# SCH_prototypeCarbon_2025-07-03.net
KiCad netlist of a schematic drawn in EasyEDA
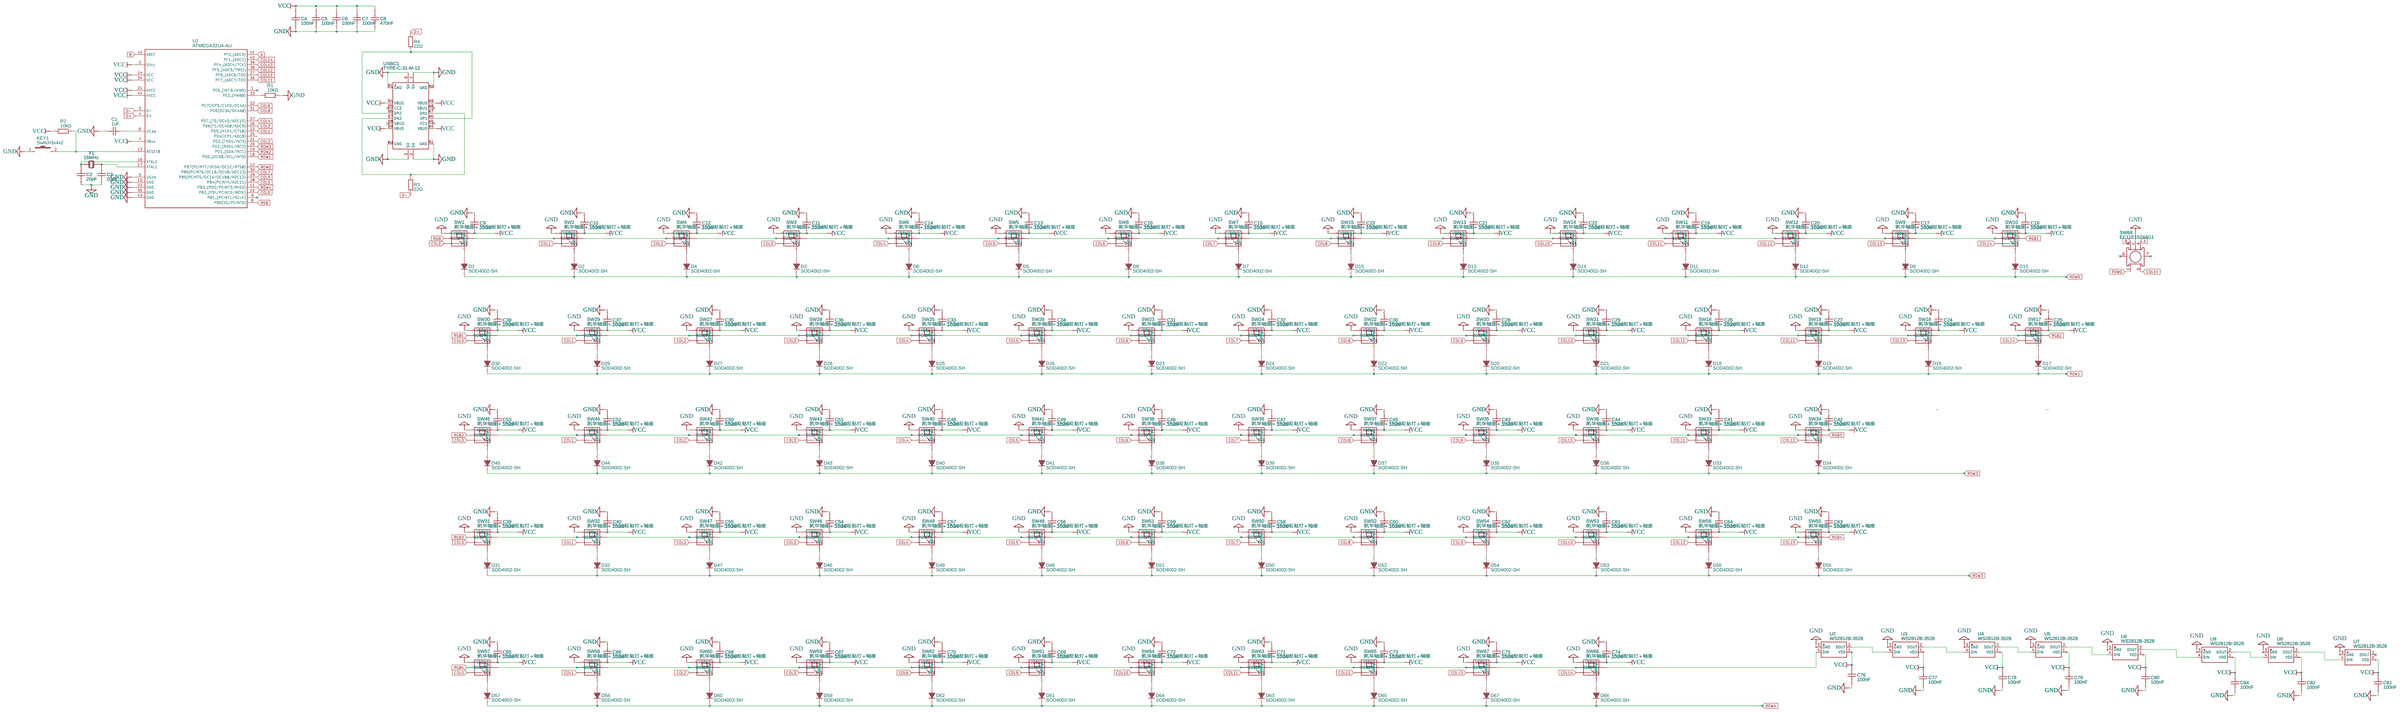
[diagram p0: schematic sheet]

(export (version "E")
  (design (tool "Eeschema 10.0.6"))
  (components
    (comp (ref "C1")
      (value "1uF")
      (fields
        (field (name "Manufacturer Part") "TCC0805X7R105K250FTA")
        (field (name "Manufacturer") "CCTC(三环)")
      )
      (libsource (lib "") (part "TCC0805X7R105K250FTA"))
    )
    (comp (ref "C2")
      (value "20pF")
      (fields
        (field (name "Manufacturer Part") "CC0805JRNPO0BN200")
        (field (name "Manufacturer") "YAGEO(国巨)")
      )
      (libsource (lib "") (part "CC0805JRNPO0BN200"))
    )
    (comp (ref "C3")
      (value "20pF")
      (fields
        (field (name "Manufacturer Part") "CC0805JRNPO0BN200")
        (field (name "Manufacturer") "YAGEO(国巨)")
      )
      (libsource (lib "") (part "CC0805JRNPO0BN200"))
    )
    (comp (ref "C4")
      (value "100nF")
      (fields
        (field (name "Manufacturer Part") "CC0805KRX7R7BB104")
        (field (name "Manufacturer") "YAGEO(国巨)")
      )
      (libsource (lib "") (part "CC0805KRX7R7BB104_1"))
    )
    (comp (ref "C5")
      (value "100nF")
      (fields
        (field (name "Manufacturer Part") "CC0805KRX7R7BB104")
        (field (name "Manufacturer") "YAGEO(国巨)")
      )
      (libsource (lib "") (part "CC0805KRX7R7BB104_1"))
    )
    (comp (ref "C6")
      (value "100nF")
      (fields
        (field (name "Manufacturer Part") "CC0805KRX7R7BB104")
        (field (name "Manufacturer") "YAGEO(国巨)")
      )
      (libsource (lib "") (part "CC0805KRX7R7BB104_1"))
    )
    (comp (ref "C7")
      (value "100nF")
      (fields
        (field (name "Manufacturer Part") "CC0805KRX7R7BB104")
        (field (name "Manufacturer") "YAGEO(国巨)")
      )
      (libsource (lib "") (part "CC0805KRX7R7BB104_1"))
    )
    (comp (ref "C8")
      (value "470nF")
      (fields
        (field (name "Manufacturer Part") "CC0805KKX7R0BB474")
        (field (name "Manufacturer") "YAGEO(国巨)")
      )
      (libsource (lib "") (part "CC0805KKX7R0BB474"))
    )
    (comp (ref "C9")
      (value "100nF")
      (fields
        (field (name "Manufacturer Part") "CC0805KRX7R7BB104")
        (field (name "Manufacturer") "YAGEO(国巨)")
      )
      (libsource (lib "") (part "CC0805KRX7R7BB104"))
    )
    (comp (ref "C10")
      (value "100nF")
      (fields
        (field (name "Manufacturer Part") "CC0805KRX7R7BB104")
        (field (name "Manufacturer") "YAGEO(国巨)")
      )
      (libsource (lib "") (part "CC0805KRX7R7BB104"))
    )
    (comp (ref "C11")
      (value "100nF")
      (fields
        (field (name "Manufacturer Part") "CC0805KRX7R7BB104")
        (field (name "Manufacturer") "YAGEO(国巨)")
      )
      (libsource (lib "") (part "CC0805KRX7R7BB104"))
    )
    (comp (ref "C12")
      (value "100nF")
      (fields
        (field (name "Manufacturer Part") "CC0805KRX7R7BB104")
        (field (name "Manufacturer") "YAGEO(国巨)")
      )
      (libsource (lib "") (part "CC0805KRX7R7BB104"))
    )
    (comp (ref "C13")
      (value "100nF")
      (fields
        (field (name "Manufacturer Part") "CC0805KRX7R7BB104")
        (field (name "Manufacturer") "YAGEO(国巨)")
      )
      (libsource (lib "") (part "CC0805KRX7R7BB104"))
    )
    (comp (ref "C14")
      (value "100nF")
      (fields
        (field (name "Manufacturer Part") "CC0805KRX7R7BB104")
        (field (name "Manufacturer") "YAGEO(国巨)")
      )
      (libsource (lib "") (part "CC0805KRX7R7BB104"))
    )
    (comp (ref "C15")
      (value "100nF")
      (fields
        (field (name "Manufacturer Part") "CC0805KRX7R7BB104")
        (field (name "Manufacturer") "YAGEO(国巨)")
      )
      (libsource (lib "") (part "CC0805KRX7R7BB104"))
    )
    (comp (ref "C16")
      (value "100nF")
      (fields
        (field (name "Manufacturer Part") "CC0805KRX7R7BB104")
        (field (name "Manufacturer") "YAGEO(国巨)")
      )
      (libsource (lib "") (part "CC0805KRX7R7BB104"))
    )
    (comp (ref "C17")
      (value "100nF")
      (fields
        (field (name "Manufacturer Part") "CC0805KRX7R7BB104")
        (field (name "Manufacturer") "YAGEO(国巨)")
      )
      (libsource (lib "") (part "CC0805KRX7R7BB104"))
    )
    (comp (ref "C18")
      (value "100nF")
      (fields
        (field (name "Manufacturer Part") "CC0805KRX7R7BB104")
        (field (name "Manufacturer") "YAGEO(国巨)")
      )
      (libsource (lib "") (part "CC0805KRX7R7BB104"))
    )
    (comp (ref "C19")
      (value "100nF")
      (fields
        (field (name "Manufacturer Part") "CC0805KRX7R7BB104")
        (field (name "Manufacturer") "YAGEO(国巨)")
      )
      (libsource (lib "") (part "CC0805KRX7R7BB104"))
    )
    (comp (ref "C20")
      (value "100nF")
      (fields
        (field (name "Manufacturer Part") "CC0805KRX7R7BB104")
        (field (name "Manufacturer") "YAGEO(国巨)")
      )
      (libsource (lib "") (part "CC0805KRX7R7BB104"))
    )
    (comp (ref "C21")
      (value "100nF")
      (fields
        (field (name "Manufacturer Part") "CC0805KRX7R7BB104")
        (field (name "Manufacturer") "YAGEO(国巨)")
      )
      (libsource (lib "") (part "CC0805KRX7R7BB104"))
    )
    (comp (ref "C22")
      (value "100nF")
      (fields
        (field (name "Manufacturer Part") "CC0805KRX7R7BB104")
        (field (name "Manufacturer") "YAGEO(国巨)")
      )
      (libsource (lib "") (part "CC0805KRX7R7BB104"))
    )
    (comp (ref "C23")
      (value "100nF")
      (fields
        (field (name "Manufacturer Part") "CC0805KRX7R7BB104")
        (field (name "Manufacturer") "YAGEO(国巨)")
      )
      (libsource (lib "") (part "CC0805KRX7R7BB104"))
    )
    (comp (ref "C24")
      (value "100nF")
      (fields
        (field (name "Manufacturer Part") "CC0805KRX7R7BB104")
        (field (name "Manufacturer") "YAGEO(国巨)")
      )
      (libsource (lib "") (part "CC0805KRX7R7BB104"))
    )
    (comp (ref "C25")
      (value "100nF")
      (fields
        (field (name "Manufacturer Part") "CC0805KRX7R7BB104")
        (field (name "Manufacturer") "YAGEO(国巨)")
      )
      (libsource (lib "") (part "CC0805KRX7R7BB104"))
    )
    (comp (ref "C26")
      (value "100nF")
      (fields
        (field (name "Manufacturer Part") "CC0805KRX7R7BB104")
        (field (name "Manufacturer") "YAGEO(国巨)")
      )
      (libsource (lib "") (part "CC0805KRX7R7BB104"))
    )
    (comp (ref "C27")
      (value "100nF")
      (fields
        (field (name "Manufacturer Part") "CC0805KRX7R7BB104")
        (field (name "Manufacturer") "YAGEO(国巨)")
      )
      (libsource (lib "") (part "CC0805KRX7R7BB104"))
    )
    (comp (ref "C28")
      (value "100nF")
      (fields
        (field (name "Manufacturer Part") "CC0805KRX7R7BB104")
        (field (name "Manufacturer") "YAGEO(国巨)")
      )
      (libsource (lib "") (part "CC0805KRX7R7BB104"))
    )
    (comp (ref "C29")
      (value "100nF")
      (fields
        (field (name "Manufacturer Part") "CC0805KRX7R7BB104")
        (field (name "Manufacturer") "YAGEO(国巨)")
      )
      (libsource (lib "") (part "CC0805KRX7R7BB104"))
    )
    (comp (ref "C30")
      (value "100nF")
      (fields
        (field (name "Manufacturer Part") "CC0805KRX7R7BB104")
        (field (name "Manufacturer") "YAGEO(国巨)")
      )
      (libsource (lib "") (part "CC0805KRX7R7BB104"))
    )
    (comp (ref "C31")
      (value "100nF")
      (fields
        (field (name "Manufacturer Part") "CC0805KRX7R7BB104")
        (field (name "Manufacturer") "YAGEO(国巨)")
      )
      (libsource (lib "") (part "CC0805KRX7R7BB104"))
    )
    (comp (ref "C32")
      (value "100nF")
      (fields
        (field (name "Manufacturer Part") "CC0805KRX7R7BB104")
        (field (name "Manufacturer") "YAGEO(国巨)")
      )
      (libsource (lib "") (part "CC0805KRX7R7BB104"))
    )
    (comp (ref "C33")
      (value "100nF")
      (fields
        (field (name "Manufacturer Part") "CC0805KRX7R7BB104")
        (field (name "Manufacturer") "YAGEO(国巨)")
      )
      (libsource (lib "") (part "CC0805KRX7R7BB104"))
    )
    (comp (ref "C34")
      (value "100nF")
      (fields
        (field (name "Manufacturer Part") "CC0805KRX7R7BB104")
        (field (name "Manufacturer") "YAGEO(国巨)")
      )
      (libsource (lib "") (part "CC0805KRX7R7BB104"))
    )
    (comp (ref "C35")
      (value "100nF")
      (fields
        (field (name "Manufacturer Part") "CC0805KRX7R7BB104")
        (field (name "Manufacturer") "YAGEO(国巨)")
      )
      (libsource (lib "") (part "CC0805KRX7R7BB104"))
    )
    (comp (ref "C36")
      (value "100nF")
      (fields
        (field (name "Manufacturer Part") "CC0805KRX7R7BB104")
        (field (name "Manufacturer") "YAGEO(国巨)")
      )
      (libsource (lib "") (part "CC0805KRX7R7BB104"))
    )
    (comp (ref "C37")
      (value "100nF")
      (fields
        (field (name "Manufacturer Part") "CC0805KRX7R7BB104")
        (field (name "Manufacturer") "YAGEO(国巨)")
      )
      (libsource (lib "") (part "CC0805KRX7R7BB104"))
    )
    (comp (ref "C38")
      (value "100nF")
      (fields
        (field (name "Manufacturer Part") "CC0805KRX7R7BB104")
        (field (name "Manufacturer") "YAGEO(国巨)")
      )
      (libsource (lib "") (part "CC0805KRX7R7BB104"))
    )
    (comp (ref "C39")
      (value "100nF")
      (fields
        (field (name "Manufacturer Part") "CC0805KRX7R7BB104")
        (field (name "Manufacturer") "YAGEO(国巨)")
      )
      (libsource (lib "") (part "CC0805KRX7R7BB104"))
    )
    (comp (ref "C40")
      (value "100nF")
      (fields
        (field (name "Manufacturer Part") "CC0805KRX7R7BB104")
        (field (name "Manufacturer") "YAGEO(国巨)")
      )
      (libsource (lib "") (part "CC0805KRX7R7BB104"))
    )
    (comp (ref "C41")
      (value "100nF")
      (fields
        (field (name "Manufacturer Part") "CC0805KRX7R7BB104")
        (field (name "Manufacturer") "YAGEO(国巨)")
      )
      (libsource (lib "") (part "CC0805KRX7R7BB104"))
    )
    (comp (ref "C42")
      (value "100nF")
      (fields
        (field (name "Manufacturer Part") "CC0805KRX7R7BB104")
        (field (name "Manufacturer") "YAGEO(国巨)")
      )
      (libsource (lib "") (part "CC0805KRX7R7BB104"))
    )
    (comp (ref "C43")
      (value "100nF")
      (fields
        (field (name "Manufacturer Part") "CC0805KRX7R7BB104")
        (field (name "Manufacturer") "YAGEO(国巨)")
      )
      (libsource (lib "") (part "CC0805KRX7R7BB104"))
    )
    (comp (ref "C44")
      (value "100nF")
      (fields
        (field (name "Manufacturer Part") "CC0805KRX7R7BB104")
        (field (name "Manufacturer") "YAGEO(国巨)")
      )
      (libsource (lib "") (part "CC0805KRX7R7BB104"))
    )
    (comp (ref "C45")
      (value "100nF")
      (fields
        (field (name "Manufacturer Part") "CC0805KRX7R7BB104")
        (field (name "Manufacturer") "YAGEO(国巨)")
      )
      (libsource (lib "") (part "CC0805KRX7R7BB104"))
    )
    (comp (ref "C46")
      (value "100nF")
      (fields
        (field (name "Manufacturer Part") "CC0805KRX7R7BB104")
        (field (name "Manufacturer") "YAGEO(国巨)")
      )
      (libsource (lib "") (part "CC0805KRX7R7BB104"))
    )
    (comp (ref "C47")
      (value "100nF")
      (fields
        (field (name "Manufacturer Part") "CC0805KRX7R7BB104")
        (field (name "Manufacturer") "YAGEO(国巨)")
      )
      (libsource (lib "") (part "CC0805KRX7R7BB104"))
    )
    (comp (ref "C48")
      (value "100nF")
      (fields
        (field (name "Manufacturer Part") "CC0805KRX7R7BB104")
        (field (name "Manufacturer") "YAGEO(国巨)")
      )
      (libsource (lib "") (part "CC0805KRX7R7BB104"))
    )
    (comp (ref "C49")
      (value "100nF")
      (fields
        (field (name "Manufacturer Part") "CC0805KRX7R7BB104")
        (field (name "Manufacturer") "YAGEO(国巨)")
      )
      (libsource (lib "") (part "CC0805KRX7R7BB104"))
    )
    (comp (ref "C50")
      (value "100nF")
      (fields
        (field (name "Manufacturer Part") "CC0805KRX7R7BB104")
        (field (name "Manufacturer") "YAGEO(国巨)")
      )
      (libsource (lib "") (part "CC0805KRX7R7BB104"))
    )
    (comp (ref "C51")
      (value "100nF")
      (fields
        (field (name "Manufacturer Part") "CC0805KRX7R7BB104")
        (field (name "Manufacturer") "YAGEO(国巨)")
      )
      (libsource (lib "") (part "CC0805KRX7R7BB104"))
    )
    (comp (ref "C52")
      (value "100nF")
      (fields
        (field (name "Manufacturer Part") "CC0805KRX7R7BB104")
        (field (name "Manufacturer") "YAGEO(国巨)")
      )
      (libsource (lib "") (part "CC0805KRX7R7BB104"))
    )
    (comp (ref "C53")
      (value "100nF")
      (fields
        (field (name "Manufacturer Part") "CC0805KRX7R7BB104")
        (field (name "Manufacturer") "YAGEO(国巨)")
      )
      (libsource (lib "") (part "CC0805KRX7R7BB104"))
    )
    (comp (ref "C54")
      (value "100nF")
      (fields
        (field (name "Manufacturer Part") "CC0805KRX7R7BB104")
        (field (name "Manufacturer") "YAGEO(国巨)")
      )
      (libsource (lib "") (part "CC0805KRX7R7BB104"))
    )
    (comp (ref "C55")
      (value "100nF")
      (fields
        (field (name "Manufacturer Part") "CC0805KRX7R7BB104")
        (field (name "Manufacturer") "YAGEO(国巨)")
      )
      (libsource (lib "") (part "CC0805KRX7R7BB104"))
    )
    (comp (ref "C56")
      (value "100nF")
      (fields
        (field (name "Manufacturer Part") "CC0805KRX7R7BB104")
        (field (name "Manufacturer") "YAGEO(国巨)")
      )
      (libsource (lib "") (part "CC0805KRX7R7BB104"))
    )
    (comp (ref "C57")
      (value "100nF")
      (fields
        (field (name "Manufacturer Part") "CC0805KRX7R7BB104")
        (field (name "Manufacturer") "YAGEO(国巨)")
      )
      (libsource (lib "") (part "CC0805KRX7R7BB104"))
    )
    (comp (ref "C58")
      (value "100nF")
      (fields
        (field (name "Manufacturer Part") "CC0805KRX7R7BB104")
        (field (name "Manufacturer") "YAGEO(国巨)")
      )
      (libsource (lib "") (part "CC0805KRX7R7BB104"))
    )
    (comp (ref "C59")
      (value "100nF")
      (fields
        (field (name "Manufacturer Part") "CC0805KRX7R7BB104")
        (field (name "Manufacturer") "YAGEO(国巨)")
      )
      (libsource (lib "") (part "CC0805KRX7R7BB104"))
    )
    (comp (ref "C60")
      (value "100nF")
      (fields
        (field (name "Manufacturer Part") "CC0805KRX7R7BB104")
        (field (name "Manufacturer") "YAGEO(国巨)")
      )
      (libsource (lib "") (part "CC0805KRX7R7BB104"))
    )
    (comp (ref "C61")
      (value "100nF")
      (fields
        (field (name "Manufacturer Part") "CC0805KRX7R7BB104")
        (field (name "Manufacturer") "YAGEO(国巨)")
      )
      (libsource (lib "") (part "CC0805KRX7R7BB104"))
    )
    (comp (ref "C62")
      (value "100nF")
      (fields
        (field (name "Manufacturer Part") "CC0805KRX7R7BB104")
        (field (name "Manufacturer") "YAGEO(国巨)")
      )
      (libsource (lib "") (part "CC0805KRX7R7BB104"))
    )
    (comp (ref "C63")
      (value "100nF")
      (fields
        (field (name "Manufacturer Part") "CC0805KRX7R7BB104")
        (field (name "Manufacturer") "YAGEO(国巨)")
      )
      (libsource (lib "") (part "CC0805KRX7R7BB104"))
    )
    (comp (ref "C64")
      (value "100nF")
      (fields
        (field (name "Manufacturer Part") "CC0805KRX7R7BB104")
        (field (name "Manufacturer") "YAGEO(国巨)")
      )
      (libsource (lib "") (part "CC0805KRX7R7BB104"))
    )
    (comp (ref "C65")
      (value "100nF")
      (fields
        (field (name "Manufacturer Part") "CC0805KRX7R7BB104")
        (field (name "Manufacturer") "YAGEO(国巨)")
      )
      (libsource (lib "") (part "CC0805KRX7R7BB104"))
    )
    (comp (ref "C66")
      (value "100nF")
      (fields
        (field (name "Manufacturer Part") "CC0805KRX7R7BB104")
        (field (name "Manufacturer") "YAGEO(国巨)")
      )
      (libsource (lib "") (part "CC0805KRX7R7BB104"))
    )
    (comp (ref "C67")
      (value "100nF")
      (fields
        (field (name "Manufacturer Part") "CC0805KRX7R7BB104")
        (field (name "Manufacturer") "YAGEO(国巨)")
      )
      (libsource (lib "") (part "CC0805KRX7R7BB104"))
    )
    (comp (ref "C68")
      (value "100nF")
      (fields
        (field (name "Manufacturer Part") "CC0805KRX7R7BB104")
        (field (name "Manufacturer") "YAGEO(国巨)")
      )
      (libsource (lib "") (part "CC0805KRX7R7BB104"))
    )
    (comp (ref "C69")
      (value "100nF")
      (fields
        (field (name "Manufacturer Part") "CC0805KRX7R7BB104")
        (field (name "Manufacturer") "YAGEO(国巨)")
      )
      (libsource (lib "") (part "CC0805KRX7R7BB104"))
    )
    (comp (ref "C70")
      (value "100nF")
      (fields
        (field (name "Manufacturer Part") "CC0805KRX7R7BB104")
        (field (name "Manufacturer") "YAGEO(国巨)")
      )
      (libsource (lib "") (part "CC0805KRX7R7BB104"))
    )
    (comp (ref "C71")
      (value "100nF")
      (fields
        (field (name "Manufacturer Part") "CC0805KRX7R7BB104")
        (field (name "Manufacturer") "YAGEO(国巨)")
      )
      (libsource (lib "") (part "CC0805KRX7R7BB104"))
    )
    (comp (ref "C72")
      (value "100nF")
      (fields
        (field (name "Manufacturer Part") "CC0805KRX7R7BB104")
        (field (name "Manufacturer") "YAGEO(国巨)")
      )
      (libsource (lib "") (part "CC0805KRX7R7BB104"))
    )
    (comp (ref "C73")
      (value "100nF")
      (fields
        (field (name "Manufacturer Part") "CC0805KRX7R7BB104")
        (field (name "Manufacturer") "YAGEO(国巨)")
      )
      (libsource (lib "") (part "CC0805KRX7R7BB104"))
    )
    (comp (ref "C74")
      (value "100nF")
      (fields
        (field (name "Manufacturer Part") "CC0805KRX7R7BB104")
        (field (name "Manufacturer") "YAGEO(国巨)")
      )
      (libsource (lib "") (part "CC0805KRX7R7BB104"))
    )
    (comp (ref "C75")
      (value "100nF")
      (fields
        (field (name "Manufacturer Part") "CC0805KRX7R7BB104")
        (field (name "Manufacturer") "YAGEO(国巨)")
      )
      (libsource (lib "") (part "CC0805KRX7R7BB104"))
    )
    (comp (ref "C76")
      (value "100nF")
      (fields
        (field (name "Manufacturer Part") "CC0805KRX7R7BB104")
        (field (name "Manufacturer") "YAGEO(国巨)")
      )
      (libsource (lib "") (part "CC0805KRX7R7BB104"))
    )
    (comp (ref "C77")
      (value "100nF")
      (fields
        (field (name "Manufacturer Part") "CC0805KRX7R7BB104")
        (field (name "Manufacturer") "YAGEO(国巨)")
      )
      (libsource (lib "") (part "CC0805KRX7R7BB104"))
    )
    (comp (ref "C78")
      (value "100nF")
      (fields
        (field (name "Manufacturer Part") "CC0805KRX7R7BB104")
        (field (name "Manufacturer") "YAGEO(国巨)")
      )
      (libsource (lib "") (part "CC0805KRX7R7BB104"))
    )
    (comp (ref "C79")
      (value "100nF")
      (fields
        (field (name "Manufacturer Part") "CC0805KRX7R7BB104")
        (field (name "Manufacturer") "YAGEO(国巨)")
      )
      (libsource (lib "") (part "CC0805KRX7R7BB104"))
    )
    (comp (ref "C80")
      (value "100nF")
      (fields
        (field (name "Manufacturer Part") "CC0805KRX7R7BB104")
        (field (name "Manufacturer") "YAGEO(国巨)")
      )
      (libsource (lib "") (part "CC0805KRX7R7BB104"))
    )
    (comp (ref "C81")
      (value "100nF")
      (fields
        (field (name "Manufacturer Part") "CC0805KRX7R7BB104")
        (field (name "Manufacturer") "YAGEO(国巨)")
      )
      (libsource (lib "") (part "CC0805KRX7R7BB104"))
    )
    (comp (ref "C82")
      (value "100nF")
      (fields
        (field (name "Manufacturer Part") "CC0805KRX7R7BB104")
        (field (name "Manufacturer") "YAGEO(国巨)")
      )
      (libsource (lib "") (part "CC0805KRX7R7BB104"))
    )
    (comp (ref "C84")
      (value "100nF")
      (fields
        (field (name "Manufacturer Part") "CC0805KRX7R7BB104")
        (field (name "Manufacturer") "YAGEO(国巨)")
      )
      (libsource (lib "") (part "CC0805KRX7R7BB104"))
    )
    (comp (ref "D1")
      (value "SOD4002-SH")
      (fields (field (name "Manufacturer") "LRC(乐山无线电)"))
      (libsource (lib "") (part "SOD4002-SH"))
    )
    (comp (ref "D2")
      (value "SOD4002-SH")
      (fields (field (name "Manufacturer") "LRC(乐山无线电)"))
      (libsource (lib "") (part "SOD4002-SH"))
    )
    (comp (ref "D3")
      (value "SOD4002-SH")
      (fields (field (name "Manufacturer") "LRC(乐山无线电)"))
      (libsource (lib "") (part "SOD4002-SH"))
    )
    (comp (ref "D4")
      (value "SOD4002-SH")
      (fields (field (name "Manufacturer") "LRC(乐山无线电)"))
      (libsource (lib "") (part "SOD4002-SH"))
    )
    (comp (ref "D5")
      (value "SOD4002-SH")
      (fields (field (name "Manufacturer") "LRC(乐山无线电)"))
      (libsource (lib "") (part "SOD4002-SH"))
    )
    (comp (ref "D6")
      (value "SOD4002-SH")
      (fields (field (name "Manufacturer") "LRC(乐山无线电)"))
      (libsource (lib "") (part "SOD4002-SH"))
    )
    (comp (ref "D7")
      (value "SOD4002-SH")
      (fields (field (name "Manufacturer") "LRC(乐山无线电)"))
      (libsource (lib "") (part "SOD4002-SH"))
    )
    (comp (ref "D8")
      (value "SOD4002-SH")
      (fields (field (name "Manufacturer") "LRC(乐山无线电)"))
      (libsource (lib "") (part "SOD4002-SH"))
    )
    (comp (ref "D9")
      (value "SOD4002-SH")
      (fields (field (name "Manufacturer") "LRC(乐山无线电)"))
      (libsource (lib "") (part "SOD4002-SH"))
    )
    (comp (ref "D10")
      (value "SOD4002-SH")
      (fields (field (name "Manufacturer") "LRC(乐山无线电)"))
      (libsource (lib "") (part "SOD4002-SH"))
    )
    (comp (ref "D11")
      (value "SOD4002-SH")
      (fields (field (name "Manufacturer") "LRC(乐山无线电)"))
      (libsource (lib "") (part "SOD4002-SH"))
    )
    (comp (ref "D12")
      (value "SOD4002-SH")
      (fields (field (name "Manufacturer") "LRC(乐山无线电)"))
      (libsource (lib "") (part "SOD4002-SH"))
    )
    (comp (ref "D13")
      (value "SOD4002-SH")
      (fields (field (name "Manufacturer") "LRC(乐山无线电)"))
      (libsource (lib "") (part "SOD4002-SH"))
    )
    (comp (ref "D14")
      (value "SOD4002-SH")
      (fields (field (name "Manufacturer") "LRC(乐山无线电)"))
      (libsource (lib "") (part "SOD4002-SH"))
    )
    (comp (ref "D15")
      (value "SOD4002-SH")
      (fields (field (name "Manufacturer") "LRC(乐山无线电)"))
      (libsource (lib "") (part "SOD4002-SH"))
    )
    (comp (ref "D16")
      (value "SOD4002-SH")
      (fields (field (name "Manufacturer") "LRC(乐山无线电)"))
      (libsource (lib "") (part "SOD4002-SH"))
    )
    (comp (ref "D17")
      (value "SOD4002-SH")
      (fields (field (name "Manufacturer") "LRC(乐山无线电)"))
      (libsource (lib "") (part "SOD4002-SH"))
    )
    (comp (ref "D18")
      (value "SOD4002-SH")
      (fields (field (name "Manufacturer") "LRC(乐山无线电)"))
      (libsource (lib "") (part "SOD4002-SH"))
    )
    (comp (ref "D19")
      (value "SOD4002-SH")
      (fields (field (name "Manufacturer") "LRC(乐山无线电)"))
      (libsource (lib "") (part "SOD4002-SH"))
    )
    (comp (ref "D20")
      (value "SOD4002-SH")
      (fields (field (name "Manufacturer") "LRC(乐山无线电)"))
      (libsource (lib "") (part "SOD4002-SH"))
    )
    (comp (ref "D21")
      (value "SOD4002-SH")
      (fields (field (name "Manufacturer") "LRC(乐山无线电)"))
      (libsource (lib "") (part "SOD4002-SH"))
    )
    (comp (ref "D22")
      (value "SOD4002-SH")
      (fields (field (name "Manufacturer") "LRC(乐山无线电)"))
      (libsource (lib "") (part "SOD4002-SH"))
    )
    (comp (ref "D23")
      (value "SOD4002-SH")
      (fields (field (name "Manufacturer") "LRC(乐山无线电)"))
      (libsource (lib "") (part "SOD4002-SH"))
    )
    (comp (ref "D24")
      (value "SOD4002-SH")
      (fields (field (name "Manufacturer") "LRC(乐山无线电)"))
      (libsource (lib "") (part "SOD4002-SH"))
    )
    (comp (ref "D25")
      (value "SOD4002-SH")
      (fields (field (name "Manufacturer") "LRC(乐山无线电)"))
      (libsource (lib "") (part "SOD4002-SH"))
    )
    (comp (ref "D26")
      (value "SOD4002-SH")
      (fields (field (name "Manufacturer") "LRC(乐山无线电)"))
      (libsource (lib "") (part "SOD4002-SH"))
    )
    (comp (ref "D27")
      (value "SOD4002-SH")
      (fields (field (name "Manufacturer") "LRC(乐山无线电)"))
      (libsource (lib "") (part "SOD4002-SH"))
    )
    (comp (ref "D28")
      (value "SOD4002-SH")
      (fields (field (name "Manufacturer") "LRC(乐山无线电)"))
      (libsource (lib "") (part "SOD4002-SH"))
    )
    (comp (ref "D29")
      (value "SOD4002-SH")
      (fields (field (name "Manufacturer") "LRC(乐山无线电)"))
      (libsource (lib "") (part "SOD4002-SH"))
    )
    (comp (ref "D30")
      (value "SOD4002-SH")
      (fields (field (name "Manufacturer") "LRC(乐山无线电)"))
      (libsource (lib "") (part "SOD4002-SH"))
    )
    (comp (ref "D31")
      (value "SOD4002-SH")
      (fields (field (name "Manufacturer") "LRC(乐山无线电)"))
      (libsource (lib "") (part "SOD4002-SH"))
    )
    (comp (ref "D32")
      (value "SOD4002-SH")
      (fields (field (name "Manufacturer") "LRC(乐山无线电)"))
      (libsource (lib "") (part "SOD4002-SH"))
    )
    (comp (ref "D33")
      (value "SOD4002-SH")
      (fields (field (name "Manufacturer") "LRC(乐山无线电)"))
      (libsource (lib "") (part "SOD4002-SH"))
    )
    (comp (ref "D34")
      (value "SOD4002-SH")
      (fields (field (name "Manufacturer") "LRC(乐山无线电)"))
      (libsource (lib "") (part "SOD4002-SH"))
    )
    (comp (ref "D35")
      (value "SOD4002-SH")
      (fields (field (name "Manufacturer") "LRC(乐山无线电)"))
      (libsource (lib "") (part "SOD4002-SH"))
    )
    (comp (ref "D36")
      (value "SOD4002-SH")
      (fields (field (name "Manufacturer") "LRC(乐山无线电)"))
      (libsource (lib "") (part "SOD4002-SH"))
    )
    (comp (ref "D37")
      (value "SOD4002-SH")
      (fields (field (name "Manufacturer") "LRC(乐山无线电)"))
      (libsource (lib "") (part "SOD4002-SH"))
    )
    (comp (ref "D38")
      (value "SOD4002-SH")
      (fields (field (name "Manufacturer") "LRC(乐山无线电)"))
      (libsource (lib "") (part "SOD4002-SH"))
    )
    (comp (ref "D39")
      (value "SOD4002-SH")
      (fields (field (name "Manufacturer") "LRC(乐山无线电)"))
      (libsource (lib "") (part "SOD4002-SH"))
    )
    (comp (ref "D40")
      (value "SOD4002-SH")
      (fields (field (name "Manufacturer") "LRC(乐山无线电)"))
      (libsource (lib "") (part "SOD4002-SH"))
    )
    (comp (ref "D41")
      (value "SOD4002-SH")
      (fields (field (name "Manufacturer") "LRC(乐山无线电)"))
      (libsource (lib "") (part "SOD4002-SH"))
    )
    (comp (ref "D42")
      (value "SOD4002-SH")
      (fields (field (name "Manufacturer") "LRC(乐山无线电)"))
      (libsource (lib "") (part "SOD4002-SH"))
    )
    (comp (ref "D43")
      (value "SOD4002-SH")
      (fields (field (name "Manufacturer") "LRC(乐山无线电)"))
      (libsource (lib "") (part "SOD4002-SH"))
    )
    (comp (ref "D44")
      (value "SOD4002-SH")
      (fields (field (name "Manufacturer") "LRC(乐山无线电)"))
      (libsource (lib "") (part "SOD4002-SH"))
    )
    (comp (ref "D45")
      (value "SOD4002-SH")
      (fields (field (name "Manufacturer") "LRC(乐山无线电)"))
      (libsource (lib "") (part "SOD4002-SH"))
    )
    (comp (ref "D46")
      (value "SOD4002-SH")
      (fields (field (name "Manufacturer") "LRC(乐山无线电)"))
      (libsource (lib "") (part "SOD4002-SH"))
    )
    (comp (ref "D47")
      (value "SOD4002-SH")
      (fields (field (name "Manufacturer") "LRC(乐山无线电)"))
      (libsource (lib "") (part "SOD4002-SH"))
    )
    (comp (ref "D48")
      (value "SOD4002-SH")
      (fields (field (name "Manufacturer") "LRC(乐山无线电)"))
      (libsource (lib "") (part "SOD4002-SH"))
    )
    (comp (ref "D49")
      (value "SOD4002-SH")
      (fields (field (name "Manufacturer") "LRC(乐山无线电)"))
      (libsource (lib "") (part "SOD4002-SH"))
    )
    (comp (ref "D50")
      (value "SOD4002-SH")
      (fields (field (name "Manufacturer") "LRC(乐山无线电)"))
      (libsource (lib "") (part "SOD4002-SH"))
    )
    (comp (ref "D51")
      (value "SOD4002-SH")
      (fields (field (name "Manufacturer") "LRC(乐山无线电)"))
      (libsource (lib "") (part "SOD4002-SH"))
    )
    (comp (ref "D52")
      (value "SOD4002-SH")
      (fields (field (name "Manufacturer") "LRC(乐山无线电)"))
      (libsource (lib "") (part "SOD4002-SH"))
    )
    (comp (ref "D53")
      (value "SOD4002-SH")
      (fields (field (name "Manufacturer") "LRC(乐山无线电)"))
      (libsource (lib "") (part "SOD4002-SH"))
    )
    (comp (ref "D54")
      (value "SOD4002-SH")
      (fields (field (name "Manufacturer") "LRC(乐山无线电)"))
      (libsource (lib "") (part "SOD4002-SH"))
    )
    (comp (ref "D55")
      (value "SOD4002-SH")
      (fields (field (name "Manufacturer") "LRC(乐山无线电)"))
      (libsource (lib "") (part "SOD4002-SH"))
    )
    (comp (ref "D56")
      (value "SOD4002-SH")
      (fields (field (name "Manufacturer") "LRC(乐山无线电)"))
      (libsource (lib "") (part "SOD4002-SH"))
    )
    (comp (ref "D57")
      (value "SOD4002-SH")
      (fields (field (name "Manufacturer") "LRC(乐山无线电)"))
      (libsource (lib "") (part "SOD4002-SH"))
    )
    (comp (ref "D58")
      (value "SOD4002-SH")
      (fields (field (name "Manufacturer") "LRC(乐山无线电)"))
      (libsource (lib "") (part "SOD4002-SH"))
    )
    (comp (ref "D59")
      (value "SOD4002-SH")
      (fields (field (name "Manufacturer") "LRC(乐山无线电)"))
      (libsource (lib "") (part "SOD4002-SH"))
    )
    (comp (ref "D60")
      (value "SOD4002-SH")
      (fields (field (name "Manufacturer") "LRC(乐山无线电)"))
      (libsource (lib "") (part "SOD4002-SH"))
    )
    (comp (ref "D61")
      (value "SOD4002-SH")
      (fields (field (name "Manufacturer") "LRC(乐山无线电)"))
      (libsource (lib "") (part "SOD4002-SH"))
    )
    (comp (ref "D62")
      (value "SOD4002-SH")
      (fields (field (name "Manufacturer") "LRC(乐山无线电)"))
      (libsource (lib "") (part "SOD4002-SH"))
    )
    (comp (ref "D63")
      (value "SOD4002-SH")
      (fields (field (name "Manufacturer") "LRC(乐山无线电)"))
      (libsource (lib "") (part "SOD4002-SH"))
    )
    (comp (ref "D64")
      (value "SOD4002-SH")
      (fields (field (name "Manufacturer") "LRC(乐山无线电)"))
      (libsource (lib "") (part "SOD4002-SH"))
    )
    (comp (ref "D65")
      (value "SOD4002-SH")
      (fields (field (name "Manufacturer") "LRC(乐山无线电)"))
      (libsource (lib "") (part "SOD4002-SH"))
    )
    (comp (ref "D66")
      (value "SOD4002-SH")
      (fields (field (name "Manufacturer") "LRC(乐山无线电)"))
      (libsource (lib "") (part "SOD4002-SH"))
    )
    (comp (ref "D67")
      (value "SOD4002-SH")
      (fields (field (name "Manufacturer") "LRC(乐山无线电)"))
      (libsource (lib "") (part "SOD4002-SH"))
    )
    (comp (ref "KEY1")
      (value "Switch3x4x2")
      (fields (field (name "Manufacturer Part") "轻触开关3x4x2") (field (name "Manufacturer") "国产"))
      (libsource (lib "") (part "Switch3x4x2"))
    )
    (comp (ref "R1")
      (value "10kΩ")
      (fields (field (name "Manufacturer Part") "AF0805FR-0710KL") (field (name "Manufacturer") "YAGEO(国巨)"))
      (libsource (lib "") (part "AF0805FR-0710KL"))
    )
    (comp (ref "R2")
      (value "10kΩ")
      (fields (field (name "Manufacturer Part") "AF0805FR-0710KL") (field (name "Manufacturer") "YAGEO(国巨)"))
      (libsource (lib "") (part "AF0805FR-0710KL"))
    )
    (comp (ref "R3")
      (value "22Ω")
      (fields (field (name "Manufacturer Part") "RT0805WRC0722RL") (field (name "Manufacturer") "YAGEO(国巨)"))
      (libsource (lib "") (part "RT0805WRC0722RL"))
    )
    (comp (ref "R4")
      (value "22Ω")
      (fields (field (name "Manufacturer Part") "RT0805WRC0722RL") (field (name "Manufacturer") "YAGEO(国巨)"))
      (libsource (lib "") (part "RT0805WRC0722RL"))
    )
    (comp (ref "SW1") (value "凯华轴座+3528反贴灯+轴座") (libsource (lib "") (part "凯华轴座+3528反贴灯+轴座")))
    (comp (ref "SW2") (value "凯华轴座+3528反贴灯+轴座") (libsource (lib "") (part "凯华轴座+3528反贴灯+轴座")))
    (comp (ref "SW3") (value "凯华轴座+3528反贴灯+轴座") (libsource (lib "") (part "凯华轴座+3528反贴灯+轴座")))
    (comp (ref "SW4") (value "凯华轴座+3528反贴灯+轴座") (libsource (lib "") (part "凯华轴座+3528反贴灯+轴座")))
    (comp (ref "SW5") (value "凯华轴座+3528反贴灯+轴座") (libsource (lib "") (part "凯华轴座+3528反贴灯+轴座")))
    (comp (ref "SW6") (value "凯华轴座+3528反贴灯+轴座") (libsource (lib "") (part "凯华轴座+3528反贴灯+轴座")))
    (comp (ref "SW7") (value "凯华轴座+3528反贴灯+轴座") (libsource (lib "") (part "凯华轴座+3528反贴灯+轴座")))
    (comp (ref "SW8") (value "凯华轴座+3528反贴灯+轴座") (libsource (lib "") (part "凯华轴座+3528反贴灯+轴座")))
    (comp (ref "SW9") (value "凯华轴座+3528反贴灯+轴座") (libsource (lib "") (part "凯华轴座+3528反贴灯+轴座")))
    (comp (ref "SW10") (value "凯华轴座+3528反贴灯+轴座") (libsource (lib "") (part "凯华轴座+3528反贴灯+轴座")))
    (comp (ref "SW11") (value "凯华轴座+3528反贴灯+轴座") (libsource (lib "") (part "凯华轴座+3528反贴灯+轴座")))
    (comp (ref "SW12") (value "凯华轴座+3528反贴灯+轴座") (libsource (lib "") (part "凯华轴座+3528反贴灯+轴座")))
    (comp (ref "SW13") (value "凯华轴座+3528反贴灯+轴座") (libsource (lib "") (part "凯华轴座+3528反贴灯+轴座")))
    (comp (ref "SW14") (value "凯华轴座+3528反贴灯+轴座") (libsource (lib "") (part "凯华轴座+3528反贴灯+轴座")))
    (comp (ref "SW15") (value "凯华轴座+3528反贴灯+轴座") (libsource (lib "") (part "凯华轴座+3528反贴灯+轴座")))
    (comp (ref "SW16") (value "凯华轴座+3528反贴灯+轴座") (libsource (lib "") (part "凯华轴座+3528反贴灯+轴座")))
    (comp (ref "SW17") (value "凯华轴座+3528反贴灯+轴座") (libsource (lib "") (part "凯华轴座+3528反贴灯+轴座")))
    (comp (ref "SW18") (value "凯华轴座+3528反贴灯+轴座") (libsource (lib "") (part "凯华轴座+3528反贴灯+轴座")))
    (comp (ref "SW19") (value "凯华轴座+3528反贴灯+轴座") (libsource (lib "") (part "凯华轴座+3528反贴灯+轴座")))
    (comp (ref "SW20") (value "凯华轴座+3528反贴灯+轴座") (libsource (lib "") (part "凯华轴座+3528反贴灯+轴座")))
    (comp (ref "SW21") (value "凯华轴座+3528反贴灯+轴座") (libsource (lib "") (part "凯华轴座+3528反贴灯+轴座")))
    (comp (ref "SW22") (value "凯华轴座+3528反贴灯+轴座") (libsource (lib "") (part "凯华轴座+3528反贴灯+轴座")))
    (comp (ref "SW23") (value "凯华轴座+3528反贴灯+轴座") (libsource (lib "") (part "凯华轴座+3528反贴灯+轴座")))
    (comp (ref "SW24") (value "凯华轴座+3528反贴灯+轴座") (libsource (lib "") (part "凯华轴座+3528反贴灯+轴座")))
    (comp (ref "SW25") (value "凯华轴座+3528反贴灯+轴座") (libsource (lib "") (part "凯华轴座+3528反贴灯+轴座")))
    (comp (ref "SW26") (value "凯华轴座+3528反贴灯+轴座") (libsource (lib "") (part "凯华轴座+3528反贴灯+轴座")))
    (comp (ref "SW27") (value "凯华轴座+3528反贴灯+轴座") (libsource (lib "") (part "凯华轴座+3528反贴灯+轴座")))
    (comp (ref "SW28") (value "凯华轴座+3528反贴灯+轴座") (libsource (lib "") (part "凯华轴座+3528反贴灯+轴座")))
    (comp (ref "SW29") (value "凯华轴座+3528反贴灯+轴座") (libsource (lib "") (part "凯华轴座+3528反贴灯+轴座")))
    (comp (ref "SW30") (value "凯华轴座+3528反贴灯+轴座") (libsource (lib "") (part "凯华轴座+3528反贴灯+轴座")))
    (comp (ref "SW31") (value "凯华轴座+3528反贴灯+轴座") (libsource (lib "") (part "凯华轴座+3528反贴灯+轴座")))
    (comp (ref "SW32") (value "凯华轴座+3528反贴灯+轴座") (libsource (lib "") (part "凯华轴座+3528反贴灯+轴座")))
    (comp (ref "SW33") (value "凯华轴座+3528反贴灯+轴座") (libsource (lib "") (part "凯华轴座+3528反贴灯+轴座")))
    (comp (ref "SW34") (value "凯华轴座+3528反贴灯+轴座") (libsource (lib "") (part "凯华轴座+3528反贴灯+轴座")))
    (comp (ref "SW35") (value "凯华轴座+3528反贴灯+轴座") (libsource (lib "") (part "凯华轴座+3528反贴灯+轴座")))
    (comp (ref "SW36") (value "凯华轴座+3528反贴灯+轴座") (libsource (lib "") (part "凯华轴座+3528反贴灯+轴座")))
    (comp (ref "SW37") (value "凯华轴座+3528反贴灯+轴座") (libsource (lib "") (part "凯华轴座+3528反贴灯+轴座")))
    (comp (ref "SW38") (value "凯华轴座+3528反贴灯+轴座") (libsource (lib "") (part "凯华轴座+3528反贴灯+轴座")))
    (comp (ref "SW39") (value "凯华轴座+3528反贴灯+轴座") (libsource (lib "") (part "凯华轴座+3528反贴灯+轴座")))
    (comp (ref "SW40") (value "凯华轴座+3528反贴灯+轴座") (libsource (lib "") (part "凯华轴座+3528反贴灯+轴座")))
    (comp (ref "SW41") (value "凯华轴座+3528反贴灯+轴座") (libsource (lib "") (part "凯华轴座+3528反贴灯+轴座")))
    (comp (ref "SW42") (value "凯华轴座+3528反贴灯+轴座") (libsource (lib "") (part "凯华轴座+3528反贴灯+轴座")))
    (comp (ref "SW43") (value "凯华轴座+3528反贴灯+轴座") (libsource (lib "") (part "凯华轴座+3528反贴灯+轴座")))
    (comp (ref "SW44") (value "凯华轴座+3528反贴灯+轴座") (libsource (lib "") (part "凯华轴座+3528反贴灯+轴座")))
    (comp (ref "SW45") (value "凯华轴座+3528反贴灯+轴座") (libsource (lib "") (part "凯华轴座+3528反贴灯+轴座")))
    (comp (ref "SW46") (value "凯华轴座+3528反贴灯+轴座") (libsource (lib "") (part "凯华轴座+3528反贴灯+轴座")))
    (comp (ref "SW47") (value "凯华轴座+3528反贴灯+轴座") (libsource (lib "") (part "凯华轴座+3528反贴灯+轴座")))
    (comp (ref "SW48") (value "凯华轴座+3528反贴灯+轴座") (libsource (lib "") (part "凯华轴座+3528反贴灯+轴座")))
    (comp (ref "SW49") (value "凯华轴座+3528反贴灯+轴座") (libsource (lib "") (part "凯华轴座+3528反贴灯+轴座")))
    (comp (ref "SW50") (value "凯华轴座+3528反贴灯+轴座") (libsource (lib "") (part "凯华轴座+3528反贴灯+轴座")))
    (comp (ref "SW51") (value "凯华轴座+3528反贴灯+轴座") (libsource (lib "") (part "凯华轴座+3528反贴灯+轴座")))
    (comp (ref "SW52") (value "凯华轴座+3528反贴灯+轴座") (libsource (lib "") (part "凯华轴座+3528反贴灯+轴座")))
    (comp (ref "SW53") (value "凯华轴座+3528反贴灯+轴座") (libsource (lib "") (part "凯华轴座+3528反贴灯+轴座")))
    (comp (ref "SW54") (value "凯华轴座+3528反贴灯+轴座") (libsource (lib "") (part "凯华轴座+3528反贴灯+轴座")))
    (comp (ref "SW55") (value "凯华轴座+3528反贴灯+轴座") (libsource (lib "") (part "凯华轴座+3528反贴灯+轴座")))
    (comp (ref "SW56") (value "凯华轴座+3528反贴灯+轴座") (libsource (lib "") (part "凯华轴座+3528反贴灯+轴座")))
    (comp (ref "SW57") (value "凯华轴座+3528反贴灯+轴座") (libsource (lib "") (part "凯华轴座+3528反贴灯+轴座")))
    (comp (ref "SW58") (value "凯华轴座+3528反贴灯+轴座") (libsource (lib "") (part "凯华轴座+3528反贴灯+轴座")))
    (comp (ref "SW59") (value "凯华轴座+3528反贴灯+轴座") (libsource (lib "") (part "凯华轴座+3528反贴灯+轴座")))
    (comp (ref "SW60") (value "凯华轴座+3528反贴灯+轴座") (libsource (lib "") (part "凯华轴座+3528反贴灯+轴座")))
    (comp (ref "SW61") (value "凯华轴座+3528反贴灯+轴座") (libsource (lib "") (part "凯华轴座+3528反贴灯+轴座")))
    (comp (ref "SW62") (value "凯华轴座+3528反贴灯+轴座") (libsource (lib "") (part "凯华轴座+3528反贴灯+轴座")))
    (comp (ref "SW63") (value "凯华轴座+3528反贴灯+轴座") (libsource (lib "") (part "凯华轴座+3528反贴灯+轴座")))
    (comp (ref "SW64") (value "凯华轴座+3528反贴灯+轴座") (libsource (lib "") (part "凯华轴座+3528反贴灯+轴座")))
    (comp (ref "SW65") (value "凯华轴座+3528反贴灯+轴座") (libsource (lib "") (part "凯华轴座+3528反贴灯+轴座")))
    (comp (ref "SW66") (value "凯华轴座+3528反贴灯+轴座") (libsource (lib "") (part "凯华轴座+3528反贴灯+轴座")))
    (comp (ref "SW67") (value "凯华轴座+3528反贴灯+轴座") (libsource (lib "") (part "凯华轴座+3528反贴灯+轴座")))
    (comp (ref "SW68")
      (value "EC11E15244G1")
      (fields (field (name "Manufacturer") "ALPSALPINE(阿尔卑斯阿尔派)"))
      (libsource (lib "") (part "EC11E15244G1"))
    )
    (comp (ref "U1")
      (value "ATMEGA32U4-AU")
      (fields (field (name "Manufacturer") "MICROCHIP(美国微芯)"))
      (libsource (lib "") (part "ATMEGA32U4-AU"))
    )
    (comp (ref "U2") (value "WS2812B-3528") (libsource (lib "") (part "WS2812B-3528")))
    (comp (ref "U3") (value "WS2812B-3528") (libsource (lib "") (part "WS2812B-3528")))
    (comp (ref "U4") (value "WS2812B-3528") (libsource (lib "") (part "WS2812B-3528")))
    (comp (ref "U5") (value "WS2812B-3528") (libsource (lib "") (part "WS2812B-3528")))
    (comp (ref "U6") (value "WS2812B-3528") (libsource (lib "") (part "WS2812B-3528")))
    (comp (ref "U7") (value "WS2812B-3528") (libsource (lib "") (part "WS2812B-3528")))
    (comp (ref "U8") (value "WS2812B-3528") (libsource (lib "") (part "WS2812B-3528")))
    (comp (ref "U9") (value "WS2812B-3528") (libsource (lib "") (part "WS2812B-3528")))
    (comp (ref "USBC1")
      (value "TYPE-C-31-M-12")
      (fields (field (name "Manufacturer") "韩国韩荣"))
      (libsource (lib "") (part "TYPE-C-31-M-12"))
    )
    (comp (ref "X1")
      (value "16MHz")
      (fields
        (field (name "Manufacturer Part") "XSHEELNANF-16MHZ")
        (field (name "Manufacturer") "TAITIEN(泰艺电子)")
      )
      (libsource (lib "") (part "XSHEELNANF-16MHZ"))
    )
  )
  (nets
    (net (code "1") (name "A") (class "Default")
      (node (ref "SW68") (pin "A") (pinfunction "A_A") (pintype "unspecified"))
      (node (ref "U1") (pin "41") (pinfunction "PF0_(ADC0)_41") (pintype "bidirectional"))
    )
    (net (code "2") (name "B") (class "Default")
      (node (ref "SW68") (pin "B") (pinfunction "B_B") (pintype "unspecified"))
      (node (ref "U1") (pin "42") (pinfunction "AREF_42") (pintype "unspecified"))
    )
    (net (code "3") (name "COL0") (class "Default")
      (node (ref "SW1") (pin "COL") (pinfunction "COL_COL") (pintype "unspecified"))
      (node (ref "SW30") (pin "COL") (pinfunction "COL_COL") (pintype "unspecified"))
      (node (ref "SW31") (pin "COL") (pinfunction "COL_COL") (pintype "unspecified"))
      (node (ref "SW45") (pin "COL") (pinfunction "COL_COL") (pintype "unspecified"))
      (node (ref "SW57") (pin "COL") (pinfunction "COL_COL") (pintype "unspecified"))
      (node (ref "U1") (pin "10") (pinfunction "PB2_(PDI/PCINT2/MOSI)_10") (pintype "bidirectional"))
    )
    (net (code "4") (name "COL1") (class "Default")
      (node (ref "SW2") (pin "COL") (pinfunction "COL_COL") (pintype "unspecified"))
      (node (ref "SW29") (pin "COL") (pinfunction "COL_COL") (pintype "unspecified"))
      (node (ref "SW32") (pin "COL") (pinfunction "COL_COL") (pintype "unspecified"))
      (node (ref "SW44") (pin "COL") (pinfunction "COL_COL") (pintype "unspecified"))
      (node (ref "SW58") (pin "COL") (pinfunction "COL_COL") (pintype "unspecified"))
      (node (ref "U1") (pin "22") (pinfunction "PD5_(XCK1/CTS#)_22") (pintype "bidirectional"))
    )
    (net (code "5") (name "COL2") (class "Default")
      (node (ref "SW27") (pin "COL") (pinfunction "COL_COL") (pintype "unspecified"))
      (node (ref "SW4") (pin "COL") (pinfunction "COL_COL") (pintype "unspecified"))
      (node (ref "SW42") (pin "COL") (pinfunction "COL_COL") (pintype "unspecified"))
      (node (ref "SW47") (pin "COL") (pinfunction "COL_COL") (pintype "unspecified"))
      (node (ref "SW60") (pin "COL") (pinfunction "COL_COL") (pintype "unspecified"))
      (node (ref "U1") (pin "21") (pinfunction "PD3_(TXD1/INT3)_21") (pintype "bidirectional"))
    )
    (net (code "6") (name "COL3") (class "Default")
      (node (ref "SW28") (pin "COL") (pinfunction "COL_COL") (pintype "unspecified"))
      (node (ref "SW3") (pin "COL") (pinfunction "COL_COL") (pintype "unspecified"))
      (node (ref "SW43") (pin "COL") (pinfunction "COL_COL") (pintype "unspecified"))
      (node (ref "SW46") (pin "COL") (pinfunction "COL_COL") (pintype "unspecified"))
      (node (ref "SW59") (pin "COL") (pinfunction "COL_COL") (pintype "unspecified"))
      (node (ref "U1") (pin "26") (pinfunction "PD6(T1/OC4D#/ADC9)_26") (pintype "bidirectional"))
    )
    (net (code "7") (name "COL4") (class "Default")
      (node (ref "SW25") (pin "COL") (pinfunction "COL_COL") (pintype "unspecified"))
      (node (ref "SW40") (pin "COL") (pinfunction "COL_COL") (pintype "unspecified"))
      (node (ref "SW49") (pin "COL") (pinfunction "COL_COL") (pintype "unspecified"))
      (node (ref "SW6") (pin "COL") (pinfunction "COL_COL") (pintype "unspecified"))
      (node (ref "U1") (pin "27") (pinfunction "PD7_(T0/OC4D/ADC10)_27") (pintype "bidirectional"))
    )
    (net (code "8") (name "COL5") (class "Default")
      (node (ref "SW26") (pin "COL") (pinfunction "COL_COL") (pintype "unspecified"))
      (node (ref "SW41") (pin "COL") (pinfunction "COL_COL") (pintype "unspecified"))
      (node (ref "SW48") (pin "COL") (pinfunction "COL_COL") (pintype "unspecified"))
      (node (ref "SW5") (pin "COL") (pinfunction "COL_COL") (pintype "unspecified"))
      (node (ref "U1") (pin "28") (pinfunction "PB4(PCINT4/ADC11)_28") (pintype "bidirectional"))
    )
    (net (code "9") (name "COL6") (class "Default")
      (node (ref "SW23") (pin "COL") (pinfunction "COL_COL") (pintype "unspecified"))
      (node (ref "SW38") (pin "COL") (pinfunction "COL_COL") (pintype "unspecified"))
      (node (ref "SW51") (pin "COL") (pinfunction "COL_COL") (pintype "unspecified"))
      (node (ref "SW62") (pin "COL") (pinfunction "COL_COL") (pintype "unspecified"))
      (node (ref "SW8") (pin "COL") (pinfunction "COL_COL") (pintype "unspecified"))
      (node (ref "U1") (pin "32") (pinfunction "PC7(ICP3/CLK0/OC4A)_32") (pintype "bidirectional"))
    )
    (net (code "10") (name "COL7") (class "Default")
      (node (ref "SW24") (pin "COL") (pinfunction "COL_COL") (pintype "unspecified"))
      (node (ref "SW39") (pin "COL") (pinfunction "COL_COL") (pintype "unspecified"))
      (node (ref "SW50") (pin "COL") (pinfunction "COL_COL") (pintype "unspecified"))
      (node (ref "SW7") (pin "COL") (pinfunction "COL_COL") (pintype "unspecified"))
      (node (ref "U1") (pin "30") (pinfunction "PB6(PCINT6/OC1B/OC4B/ADC13)_30") (pintype "bidirectional"))
    )
    (net (code "11") (name "COL8") (class "Default")
      (node (ref "SW15") (pin "COL") (pinfunction "COL_COL") (pintype "unspecified"))
      (node (ref "SW22") (pin "COL") (pinfunction "COL_COL") (pintype "unspecified"))
      (node (ref "SW37") (pin "COL") (pinfunction "COL_COL") (pintype "unspecified"))
      (node (ref "SW52") (pin "COL") (pinfunction "COL_COL") (pintype "unspecified"))
      (node (ref "U1") (pin "31") (pinfunction "PC6(OC3A/OC4A#)_31") (pintype "bidirectional"))
    )
    (net (code "12") (name "COL9") (class "Default")
      (node (ref "SW13") (pin "COL") (pinfunction "COL_COL") (pintype "unspecified"))
      (node (ref "SW20") (pin "COL") (pinfunction "COL_COL") (pintype "unspecified"))
      (node (ref "SW35") (pin "COL") (pinfunction "COL_COL") (pintype "unspecified"))
      (node (ref "SW54") (pin "COL") (pinfunction "COL_COL") (pintype "unspecified"))
      (node (ref "SW61") (pin "COL") (pinfunction "COL_COL") (pintype "unspecified"))
      (node (ref "U1") (pin "29") (pinfunction "PB5(PCINT5/OC1A/OC4B#/ADC12)_29") (pintype "bidirectional"))
    )
    (net (code "13") (name "COL10") (class "Default")
      (node (ref "SW14") (pin "COL") (pinfunction "COL_COL") (pintype "unspecified"))
      (node (ref "SW21") (pin "COL") (pinfunction "COL_COL") (pintype "unspecified"))
      (node (ref "SW36") (pin "COL") (pinfunction "COL_COL") (pintype "unspecified"))
      (node (ref "SW53") (pin "COL") (pinfunction "COL_COL") (pintype "unspecified"))
      (node (ref "SW64") (pin "COL") (pinfunction "COL_COL") (pintype "unspecified"))
      (node (ref "U1") (pin "37") (pinfunction "PF6_(ADC6/TDO_37") (pintype "bidirectional"))
    )
    (net (code "14") (name "COL11") (class "Default")
      (node (ref "SW11") (pin "COL") (pinfunction "COL_COL") (pintype "unspecified"))
      (node (ref "SW18") (pin "COL") (pinfunction "COL_COL") (pintype "unspecified"))
      (node (ref "SW33") (pin "COL") (pinfunction "COL_COL") (pintype "unspecified"))
      (node (ref "SW63") (pin "COL") (pinfunction "COL_COL") (pintype "unspecified"))
      (node (ref "U1") (pin "36") (pinfunction "PF7_(ADC7/TDI)_36") (pintype "bidirectional"))
    )
    (net (code "15") (name "COL12") (class "Default")
      (node (ref "SW12") (pin "COL") (pinfunction "COL_COL") (pintype "unspecified"))
      (node (ref "SW19") (pin "COL") (pinfunction "COL_COL") (pintype "unspecified"))
      (node (ref "SW34") (pin "COL") (pinfunction "COL_COL") (pintype "unspecified"))
      (node (ref "SW56") (pin "COL") (pinfunction "COL_COL") (pintype "unspecified"))
      (node (ref "SW65") (pin "COL") (pinfunction "COL_COL") (pintype "unspecified"))
      (node (ref "U1") (pin "38") (pinfunction "PF5_(ADC5/TMS))_38") (pintype "bidirectional"))
    )
    (net (code "16") (name "COL13") (class "Default")
      (node (ref "SW16") (pin "COL") (pinfunction "COL_COL") (pintype "unspecified"))
      (node (ref "SW55") (pin "COL") (pinfunction "COL_COL") (pintype "unspecified"))
      (node (ref "SW67") (pin "COL") (pinfunction "COL_COL") (pintype "unspecified"))
      (node (ref "SW9") (pin "COL") (pinfunction "COL_COL") (pintype "unspecified"))
      (node (ref "U1") (pin "39") (pinfunction "PF4_(ADC4/TCK)_39") (pintype "bidirectional"))
    )
    (net (code "17") (name "COL14") (class "Default")
      (node (ref "SW10") (pin "COL") (pinfunction "COL_COL") (pintype "unspecified"))
      (node (ref "SW17") (pin "COL") (pinfunction "COL_COL") (pintype "unspecified"))
      (node (ref "SW66") (pin "COL") (pinfunction "COL_COL") (pintype "unspecified"))
      (node (ref "SW68") (pin "D") (pinfunction "D_D") (pintype "unspecified"))
      (node (ref "U1") (pin "40") (pinfunction "PF1_(ADC1)_40") (pintype "bidirectional"))
    )
    (net (code "18") (name "D+") (class "Default")
      (node (ref "R4") (pin "2") (pinfunction "2_2") (pintype "input"))
      (node (ref "U1") (pin "4") (pinfunction "D+_4") (pintype "bidirectional"))
    )
    (net (code "19") (name "D-") (class "Default")
      (node (ref "R3") (pin "1") (pinfunction "1_1") (pintype "input"))
      (node (ref "U1") (pin "3") (pinfunction "D-_3") (pintype "bidirectional"))
    )
    (net (code "20") (name "GND") (class "Default")
      (node (ref "C1") (pin "2") (pinfunction "2_2") (pintype "unspecified"))
      (node (ref "C10") (pin "2") (pinfunction "2_2") (pintype "unspecified"))
      (node (ref "C11") (pin "2") (pinfunction "2_2") (pintype "unspecified"))
      (node (ref "C12") (pin "2") (pinfunction "2_2") (pintype "unspecified"))
      (node (ref "C13") (pin "2") (pinfunction "2_2") (pintype "unspecified"))
      (node (ref "C14") (pin "2") (pinfunction "2_2") (pintype "unspecified"))
      (node (ref "C15") (pin "2") (pinfunction "2_2") (pintype "unspecified"))
      (node (ref "C16") (pin "2") (pinfunction "2_2") (pintype "unspecified"))
      (node (ref "C17") (pin "2") (pinfunction "2_2") (pintype "unspecified"))
      (node (ref "C18") (pin "2") (pinfunction "2_2") (pintype "unspecified"))
      (node (ref "C19") (pin "2") (pinfunction "2_2") (pintype "unspecified"))
      (node (ref "C2") (pin "2") (pinfunction "2_2") (pintype "unspecified"))
      (node (ref "C20") (pin "2") (pinfunction "2_2") (pintype "unspecified"))
      (node (ref "C21") (pin "2") (pinfunction "2_2") (pintype "unspecified"))
      (node (ref "C22") (pin "2") (pinfunction "2_2") (pintype "unspecified"))
      (node (ref "C23") (pin "2") (pinfunction "2_2") (pintype "unspecified"))
      (node (ref "C24") (pin "2") (pinfunction "2_2") (pintype "unspecified"))
      (node (ref "C25") (pin "2") (pinfunction "2_2") (pintype "unspecified"))
      (node (ref "C26") (pin "2") (pinfunction "2_2") (pintype "unspecified"))
      (node (ref "C27") (pin "2") (pinfunction "2_2") (pintype "unspecified"))
      (node (ref "C28") (pin "2") (pinfunction "2_2") (pintype "unspecified"))
      (node (ref "C29") (pin "2") (pinfunction "2_2") (pintype "unspecified"))
      (node (ref "C3") (pin "2") (pinfunction "2_2") (pintype "unspecified"))
      (node (ref "C30") (pin "2") (pinfunction "2_2") (pintype "unspecified"))
      (node (ref "C31") (pin "2") (pinfunction "2_2") (pintype "unspecified"))
      (node (ref "C32") (pin "2") (pinfunction "2_2") (pintype "unspecified"))
      (node (ref "C33") (pin "2") (pinfunction "2_2") (pintype "unspecified"))
      (node (ref "C34") (pin "2") (pinfunction "2_2") (pintype "unspecified"))
      (node (ref "C35") (pin "2") (pinfunction "2_2") (pintype "unspecified"))
      (node (ref "C36") (pin "2") (pinfunction "2_2") (pintype "unspecified"))
      (node (ref "C37") (pin "2") (pinfunction "2_2") (pintype "unspecified"))
      (node (ref "C38") (pin "2") (pinfunction "2_2") (pintype "unspecified"))
      (node (ref "C39") (pin "2") (pinfunction "2_2") (pintype "unspecified"))
      (node (ref "C4") (pin "2") (pinfunction "2_2") (pintype "unspecified"))
      (node (ref "C40") (pin "2") (pinfunction "2_2") (pintype "unspecified"))
      (node (ref "C41") (pin "2") (pinfunction "2_2") (pintype "unspecified"))
      (node (ref "C42") (pin "2") (pinfunction "2_2") (pintype "unspecified"))
      (node (ref "C43") (pin "2") (pinfunction "2_2") (pintype "unspecified"))
      (node (ref "C44") (pin "2") (pinfunction "2_2") (pintype "unspecified"))
      (node (ref "C45") (pin "2") (pinfunction "2_2") (pintype "unspecified"))
      (node (ref "C46") (pin "2") (pinfunction "2_2") (pintype "unspecified"))
      (node (ref "C47") (pin "2") (pinfunction "2_2") (pintype "unspecified"))
      (node (ref "C48") (pin "2") (pinfunction "2_2") (pintype "unspecified"))
      (node (ref "C49") (pin "2") (pinfunction "2_2") (pintype "unspecified"))
      (node (ref "C5") (pin "2") (pinfunction "2_2") (pintype "unspecified"))
      (node (ref "C50") (pin "2") (pinfunction "2_2") (pintype "unspecified"))
      (node (ref "C51") (pin "2") (pinfunction "2_2") (pintype "unspecified"))
      (node (ref "C52") (pin "2") (pinfunction "2_2") (pintype "unspecified"))
      (node (ref "C53") (pin "2") (pinfunction "2_2") (pintype "unspecified"))
      (node (ref "C54") (pin "2") (pinfunction "2_2") (pintype "unspecified"))
      (node (ref "C55") (pin "2") (pinfunction "2_2") (pintype "unspecified"))
      (node (ref "C56") (pin "2") (pinfunction "2_2") (pintype "unspecified"))
      (node (ref "C57") (pin "2") (pinfunction "2_2") (pintype "unspecified"))
      (node (ref "C58") (pin "2") (pinfunction "2_2") (pintype "unspecified"))
      (node (ref "C59") (pin "2") (pinfunction "2_2") (pintype "unspecified"))
      (node (ref "C6") (pin "2") (pinfunction "2_2") (pintype "unspecified"))
      (node (ref "C60") (pin "2") (pinfunction "2_2") (pintype "unspecified"))
      (node (ref "C61") (pin "2") (pinfunction "2_2") (pintype "unspecified"))
      (node (ref "C62") (pin "2") (pinfunction "2_2") (pintype "unspecified"))
      (node (ref "C63") (pin "2") (pinfunction "2_2") (pintype "unspecified"))
      (node (ref "C64") (pin "2") (pinfunction "2_2") (pintype "unspecified"))
      (node (ref "C65") (pin "2") (pinfunction "2_2") (pintype "unspecified"))
      (node (ref "C66") (pin "2") (pinfunction "2_2") (pintype "unspecified"))
      (node (ref "C67") (pin "2") (pinfunction "2_2") (pintype "unspecified"))
      (node (ref "C68") (pin "2") (pinfunction "2_2") (pintype "unspecified"))
      (node (ref "C69") (pin "2") (pinfunction "2_2") (pintype "unspecified"))
      (node (ref "C7") (pin "2") (pinfunction "2_2") (pintype "unspecified"))
      (node (ref "C70") (pin "2") (pinfunction "2_2") (pintype "unspecified"))
      (node (ref "C71") (pin "2") (pinfunction "2_2") (pintype "unspecified"))
      (node (ref "C72") (pin "2") (pinfunction "2_2") (pintype "unspecified"))
      (node (ref "C73") (pin "2") (pinfunction "2_2") (pintype "unspecified"))
      (node (ref "C74") (pin "2") (pinfunction "2_2") (pintype "unspecified"))
      (node (ref "C75") (pin "2") (pinfunction "2_2") (pintype "unspecified"))
      (node (ref "C76") (pin "1") (pinfunction "1_1") (pintype "unspecified"))
      (node (ref "C77") (pin "1") (pinfunction "1_1") (pintype "unspecified"))
      (node (ref "C78") (pin "1") (pinfunction "1_1") (pintype "unspecified"))
      (node (ref "C79") (pin "1") (pinfunction "1_1") (pintype "unspecified"))
      (node (ref "C8") (pin "1") (pinfunction "1_1") (pintype "unspecified"))
      (node (ref "C80") (pin "1") (pinfunction "1_1") (pintype "unspecified"))
      (node (ref "C81") (pin "1") (pinfunction "1_1") (pintype "unspecified"))
      (node (ref "C82") (pin "1") (pinfunction "1_1") (pintype "unspecified"))
      (node (ref "C84") (pin "1") (pinfunction "1_1") (pintype "unspecified"))
      (node (ref "C9") (pin "2") (pinfunction "2_2") (pintype "unspecified"))
      (node (ref "KEY1") (pin "1") (pinfunction "1_1") (pintype "input"))
      (node (ref "R1") (pin "2") (pinfunction "2_2") (pintype "unspecified"))
      (node (ref "SW1") (pin "GND") (pinfunction "GND_GND") (pintype "unspecified"))
      (node (ref "SW10") (pin "GND") (pinfunction "GND_GND") (pintype "unspecified"))
      (node (ref "SW11") (pin "GND") (pinfunction "GND_GND") (pintype "unspecified"))
      (node (ref "SW12") (pin "GND") (pinfunction "GND_GND") (pintype "unspecified"))
      (node (ref "SW13") (pin "GND") (pinfunction "GND_GND") (pintype "unspecified"))
      (node (ref "SW14") (pin "GND") (pinfunction "GND_GND") (pintype "unspecified"))
      (node (ref "SW15") (pin "GND") (pinfunction "GND_GND") (pintype "unspecified"))
      (node (ref "SW16") (pin "GND") (pinfunction "GND_GND") (pintype "unspecified"))
      (node (ref "SW17") (pin "GND") (pinfunction "GND_GND") (pintype "unspecified"))
      (node (ref "SW18") (pin "GND") (pinfunction "GND_GND") (pintype "unspecified"))
      (node (ref "SW19") (pin "GND") (pinfunction "GND_GND") (pintype "unspecified"))
      (node (ref "SW2") (pin "GND") (pinfunction "GND_GND") (pintype "unspecified"))
      (node (ref "SW20") (pin "GND") (pinfunction "GND_GND") (pintype "unspecified"))
      (node (ref "SW21") (pin "GND") (pinfunction "GND_GND") (pintype "unspecified"))
      (node (ref "SW22") (pin "GND") (pinfunction "GND_GND") (pintype "unspecified"))
      (node (ref "SW23") (pin "GND") (pinfunction "GND_GND") (pintype "unspecified"))
      (node (ref "SW24") (pin "GND") (pinfunction "GND_GND") (pintype "unspecified"))
      (node (ref "SW25") (pin "GND") (pinfunction "GND_GND") (pintype "unspecified"))
      (node (ref "SW26") (pin "GND") (pinfunction "GND_GND") (pintype "unspecified"))
      (node (ref "SW27") (pin "GND") (pinfunction "GND_GND") (pintype "unspecified"))
      (node (ref "SW28") (pin "GND") (pinfunction "GND_GND") (pintype "unspecified"))
      (node (ref "SW29") (pin "GND") (pinfunction "GND_GND") (pintype "unspecified"))
      (node (ref "SW3") (pin "GND") (pinfunction "GND_GND") (pintype "unspecified"))
      (node (ref "SW30") (pin "GND") (pinfunction "GND_GND") (pintype "unspecified"))
      (node (ref "SW31") (pin "GND") (pinfunction "GND_GND") (pintype "unspecified"))
      (node (ref "SW32") (pin "GND") (pinfunction "GND_GND") (pintype "unspecified"))
      (node (ref "SW33") (pin "GND") (pinfunction "GND_GND") (pintype "unspecified"))
      (node (ref "SW34") (pin "GND") (pinfunction "GND_GND") (pintype "unspecified"))
      (node (ref "SW35") (pin "GND") (pinfunction "GND_GND") (pintype "unspecified"))
      (node (ref "SW36") (pin "GND") (pinfunction "GND_GND") (pintype "unspecified"))
      (node (ref "SW37") (pin "GND") (pinfunction "GND_GND") (pintype "unspecified"))
      (node (ref "SW38") (pin "GND") (pinfunction "GND_GND") (pintype "unspecified"))
      (node (ref "SW39") (pin "GND") (pinfunction "GND_GND") (pintype "unspecified"))
      (node (ref "SW4") (pin "GND") (pinfunction "GND_GND") (pintype "unspecified"))
      (node (ref "SW40") (pin "GND") (pinfunction "GND_GND") (pintype "unspecified"))
      (node (ref "SW41") (pin "GND") (pinfunction "GND_GND") (pintype "unspecified"))
      (node (ref "SW42") (pin "GND") (pinfunction "GND_GND") (pintype "unspecified"))
      (node (ref "SW43") (pin "GND") (pinfunction "GND_GND") (pintype "unspecified"))
      (node (ref "SW44") (pin "GND") (pinfunction "GND_GND") (pintype "unspecified"))
      (node (ref "SW45") (pin "GND") (pinfunction "GND_GND") (pintype "unspecified"))
      (node (ref "SW46") (pin "GND") (pinfunction "GND_GND") (pintype "unspecified"))
      (node (ref "SW47") (pin "GND") (pinfunction "GND_GND") (pintype "unspecified"))
      (node (ref "SW48") (pin "GND") (pinfunction "GND_GND") (pintype "unspecified"))
      (node (ref "SW49") (pin "GND") (pinfunction "GND_GND") (pintype "unspecified"))
      (node (ref "SW5") (pin "GND") (pinfunction "GND_GND") (pintype "unspecified"))
      (node (ref "SW50") (pin "GND") (pinfunction "GND_GND") (pintype "unspecified"))
      (node (ref "SW51") (pin "GND") (pinfunction "GND_GND") (pintype "unspecified"))
      (node (ref "SW52") (pin "GND") (pinfunction "GND_GND") (pintype "unspecified"))
      (node (ref "SW53") (pin "GND") (pinfunction "GND_GND") (pintype "unspecified"))
      (node (ref "SW54") (pin "GND") (pinfunction "GND_GND") (pintype "unspecified"))
      (node (ref "SW55") (pin "GND") (pinfunction "GND_GND") (pintype "unspecified"))
      (node (ref "SW56") (pin "GND") (pinfunction "GND_GND") (pintype "unspecified"))
      (node (ref "SW57") (pin "GND") (pinfunction "GND_GND") (pintype "unspecified"))
      (node (ref "SW58") (pin "GND") (pinfunction "GND_GND") (pintype "unspecified"))
      (node (ref "SW59") (pin "GND") (pinfunction "GND_GND") (pintype "unspecified"))
      (node (ref "SW6") (pin "GND") (pinfunction "GND_GND") (pintype "unspecified"))
      (node (ref "SW60") (pin "GND") (pinfunction "GND_GND") (pintype "unspecified"))
      (node (ref "SW61") (pin "GND") (pinfunction "GND_GND") (pintype "unspecified"))
      (node (ref "SW62") (pin "GND") (pinfunction "GND_GND") (pintype "unspecified"))
      (node (ref "SW63") (pin "GND") (pinfunction "GND_GND") (pintype "unspecified"))
      (node (ref "SW64") (pin "GND") (pinfunction "GND_GND") (pintype "unspecified"))
      (node (ref "SW65") (pin "GND") (pinfunction "GND_GND") (pintype "unspecified"))
      (node (ref "SW66") (pin "GND") (pinfunction "GND_GND") (pintype "unspecified"))
      (node (ref "SW67") (pin "GND") (pinfunction "GND_GND") (pintype "unspecified"))
      (node (ref "SW68") (pin "C") (pinfunction "C_C") (pintype "unspecified"))
      (node (ref "SW7") (pin "GND") (pinfunction "GND_GND") (pintype "unspecified"))
      (node (ref "SW8") (pin "GND") (pinfunction "GND_GND") (pintype "unspecified"))
      (node (ref "SW9") (pin "GND") (pinfunction "GND_GND") (pintype "unspecified"))
      (node (ref "U1") (pin "15") (pinfunction "GND_15") (pintype "passive"))
      (node (ref "U1") (pin "23") (pinfunction "GND_23") (pintype "passive"))
      (node (ref "U1") (pin "35") (pinfunction "GND_35") (pintype "passive"))
      (node (ref "U1") (pin "43") (pinfunction "GND_43") (pintype "passive"))
      (node (ref "U1") (pin "5") (pinfunction "UGnd_5") (pintype "passive"))
      (node (ref "U2") (pin "3") (pinfunction "GND_3") (pintype "unspecified"))
      (node (ref "U3") (pin "3") (pinfunction "GND_3") (pintype "unspecified"))
      (node (ref "U4") (pin "3") (pinfunction "GND_3") (pintype "unspecified"))
      (node (ref "U5") (pin "3") (pinfunction "GND_3") (pintype "unspecified"))
      (node (ref "U6") (pin "3") (pinfunction "GND_3") (pintype "unspecified"))
      (node (ref "U7") (pin "3") (pinfunction "GND_3") (pintype "unspecified"))
      (node (ref "U8") (pin "3") (pinfunction "GND_3") (pintype "unspecified"))
      (node (ref "U9") (pin "3") (pinfunction "GND_3") (pintype "unspecified"))
      (node (ref "USBC1") (pin "0") (pinfunction "SH_0") (pintype "unspecified"))
      (node (ref "USBC1") (pin "1") (pinfunction "SH_1") (pintype "unspecified"))
      (node (ref "USBC1") (pin "2") (pinfunction "SH_2") (pintype "unspecified"))
      (node (ref "USBC1") (pin "3") (pinfunction "SH_3") (pintype "unspecified"))
      (node (ref "USBC1") (pin "A1") (pinfunction "GND_A1") (pintype "unspecified"))
      (node (ref "USBC1") (pin "A12") (pinfunction "GND_A12") (pintype "unspecified"))
      (node (ref "USBC1") (pin "B1") (pinfunction "GND_B1") (pintype "unspecified"))
      (node (ref "USBC1") (pin "B12") (pinfunction "GND_B12") (pintype "unspecified"))
    )
    (net (code "21") (name "Net-(D1-A)") (class "Default")
      (node (ref "D1") (pin "2") (pinfunction "A_2") (pintype "unspecified"))
      (node (ref "SW1") (pin "ROW") (pinfunction "ROW_ROW") (pintype "unspecified"))
    )
    (net (code "22") (name "Net-(D2-A)") (class "Default")
      (node (ref "D2") (pin "2") (pinfunction "A_2") (pintype "unspecified"))
      (node (ref "SW2") (pin "ROW") (pinfunction "ROW_ROW") (pintype "unspecified"))
    )
    (net (code "23") (name "Net-(D3-A)") (class "Default")
      (node (ref "D3") (pin "2") (pinfunction "A_2") (pintype "unspecified"))
      (node (ref "SW3") (pin "ROW") (pinfunction "ROW_ROW") (pintype "unspecified"))
    )
    (net (code "24") (name "Net-(D4-A)") (class "Default")
      (node (ref "D4") (pin "2") (pinfunction "A_2") (pintype "unspecified"))
      (node (ref "SW4") (pin "ROW") (pinfunction "ROW_ROW") (pintype "unspecified"))
    )
    (net (code "25") (name "Net-(D5-A)") (class "Default")
      (node (ref "D5") (pin "2") (pinfunction "A_2") (pintype "unspecified"))
      (node (ref "SW5") (pin "ROW") (pinfunction "ROW_ROW") (pintype "unspecified"))
    )
    (net (code "26") (name "Net-(D6-A)") (class "Default")
      (node (ref "D6") (pin "2") (pinfunction "A_2") (pintype "unspecified"))
      (node (ref "SW6") (pin "ROW") (pinfunction "ROW_ROW") (pintype "unspecified"))
    )
    (net (code "27") (name "Net-(D7-A)") (class "Default")
      (node (ref "D7") (pin "2") (pinfunction "A_2") (pintype "unspecified"))
      (node (ref "SW7") (pin "ROW") (pinfunction "ROW_ROW") (pintype "unspecified"))
    )
    (net (code "28") (name "Net-(D8-A)") (class "Default")
      (node (ref "D8") (pin "2") (pinfunction "A_2") (pintype "unspecified"))
      (node (ref "SW8") (pin "ROW") (pinfunction "ROW_ROW") (pintype "unspecified"))
    )
    (net (code "29") (name "Net-(D9-A)") (class "Default")
      (node (ref "D9") (pin "2") (pinfunction "A_2") (pintype "unspecified"))
      (node (ref "SW9") (pin "ROW") (pinfunction "ROW_ROW") (pintype "unspecified"))
    )
    (net (code "30") (name "Net-(D10-A)") (class "Default")
      (node (ref "D10") (pin "2") (pinfunction "A_2") (pintype "unspecified"))
      (node (ref "SW10") (pin "ROW") (pinfunction "ROW_ROW") (pintype "unspecified"))
    )
    (net (code "31") (name "Net-(D11-A)") (class "Default")
      (node (ref "D11") (pin "2") (pinfunction "A_2") (pintype "unspecified"))
      (node (ref "SW11") (pin "ROW") (pinfunction "ROW_ROW") (pintype "unspecified"))
    )
    (net (code "32") (name "Net-(D12-A)") (class "Default")
      (node (ref "D12") (pin "2") (pinfunction "A_2") (pintype "unspecified"))
      (node (ref "SW12") (pin "ROW") (pinfunction "ROW_ROW") (pintype "unspecified"))
    )
    (net (code "33") (name "Net-(D13-A)") (class "Default")
      (node (ref "D13") (pin "2") (pinfunction "A_2") (pintype "unspecified"))
      (node (ref "SW13") (pin "ROW") (pinfunction "ROW_ROW") (pintype "unspecified"))
    )
    (net (code "34") (name "Net-(D14-A)") (class "Default")
      (node (ref "D14") (pin "2") (pinfunction "A_2") (pintype "unspecified"))
      (node (ref "SW14") (pin "ROW") (pinfunction "ROW_ROW") (pintype "unspecified"))
    )
    (net (code "35") (name "Net-(D15-A)") (class "Default")
      (node (ref "D15") (pin "2") (pinfunction "A_2") (pintype "unspecified"))
      (node (ref "SW15") (pin "ROW") (pinfunction "ROW_ROW") (pintype "unspecified"))
    )
    (net (code "36") (name "Net-(D16-A)") (class "Default")
      (node (ref "D16") (pin "2") (pinfunction "A_2") (pintype "unspecified"))
      (node (ref "SW16") (pin "ROW") (pinfunction "ROW_ROW") (pintype "unspecified"))
    )
    (net (code "37") (name "Net-(D17-A)") (class "Default")
      (node (ref "D17") (pin "2") (pinfunction "A_2") (pintype "unspecified"))
      (node (ref "SW17") (pin "ROW") (pinfunction "ROW_ROW") (pintype "unspecified"))
    )
    (net (code "38") (name "Net-(D18-A)") (class "Default")
      (node (ref "D18") (pin "2") (pinfunction "A_2") (pintype "unspecified"))
      (node (ref "SW18") (pin "ROW") (pinfunction "ROW_ROW") (pintype "unspecified"))
    )
    (net (code "39") (name "Net-(D19-A)") (class "Default")
      (node (ref "D19") (pin "2") (pinfunction "A_2") (pintype "unspecified"))
      (node (ref "SW19") (pin "ROW") (pinfunction "ROW_ROW") (pintype "unspecified"))
    )
    (net (code "40") (name "Net-(D20-A)") (class "Default")
      (node (ref "D20") (pin "2") (pinfunction "A_2") (pintype "unspecified"))
      (node (ref "SW20") (pin "ROW") (pinfunction "ROW_ROW") (pintype "unspecified"))
    )
    (net (code "41") (name "Net-(D21-A)") (class "Default")
      (node (ref "D21") (pin "2") (pinfunction "A_2") (pintype "unspecified"))
      (node (ref "SW21") (pin "ROW") (pinfunction "ROW_ROW") (pintype "unspecified"))
    )
    (net (code "42") (name "Net-(D22-A)") (class "Default")
      (node (ref "D22") (pin "2") (pinfunction "A_2") (pintype "unspecified"))
      (node (ref "SW22") (pin "ROW") (pinfunction "ROW_ROW") (pintype "unspecified"))
    )
    (net (code "43") (name "Net-(D23-A)") (class "Default")
      (node (ref "D23") (pin "2") (pinfunction "A_2") (pintype "unspecified"))
      (node (ref "SW23") (pin "ROW") (pinfunction "ROW_ROW") (pintype "unspecified"))
    )
    (net (code "44") (name "Net-(D24-A)") (class "Default")
      (node (ref "D24") (pin "2") (pinfunction "A_2") (pintype "unspecified"))
      (node (ref "SW24") (pin "ROW") (pinfunction "ROW_ROW") (pintype "unspecified"))
    )
    (net (code "45") (name "Net-(D25-A)") (class "Default")
      (node (ref "D25") (pin "2") (pinfunction "A_2") (pintype "unspecified"))
      (node (ref "SW25") (pin "ROW") (pinfunction "ROW_ROW") (pintype "unspecified"))
    )
    (net (code "46") (name "Net-(D26-A)") (class "Default")
      (node (ref "D26") (pin "2") (pinfunction "A_2") (pintype "unspecified"))
      (node (ref "SW26") (pin "ROW") (pinfunction "ROW_ROW") (pintype "unspecified"))
    )
    (net (code "47") (name "Net-(D27-A)") (class "Default")
      (node (ref "D27") (pin "2") (pinfunction "A_2") (pintype "unspecified"))
      (node (ref "SW27") (pin "ROW") (pinfunction "ROW_ROW") (pintype "unspecified"))
    )
    (net (code "48") (name "Net-(D28-A)") (class "Default")
      (node (ref "D28") (pin "2") (pinfunction "A_2") (pintype "unspecified"))
      (node (ref "SW28") (pin "ROW") (pinfunction "ROW_ROW") (pintype "unspecified"))
    )
    (net (code "49") (name "Net-(D29-A)") (class "Default")
      (node (ref "D29") (pin "2") (pinfunction "A_2") (pintype "unspecified"))
      (node (ref "SW29") (pin "ROW") (pinfunction "ROW_ROW") (pintype "unspecified"))
    )
    (net (code "50") (name "Net-(D30-A)") (class "Default")
      (node (ref "D30") (pin "2") (pinfunction "A_2") (pintype "unspecified"))
      (node (ref "SW30") (pin "ROW") (pinfunction "ROW_ROW") (pintype "unspecified"))
    )
    (net (code "51") (name "Net-(D31-A)") (class "Default")
      (node (ref "D31") (pin "2") (pinfunction "A_2") (pintype "unspecified"))
      (node (ref "SW31") (pin "ROW") (pinfunction "ROW_ROW") (pintype "unspecified"))
    )
    (net (code "52") (name "Net-(D32-A)") (class "Default")
      (node (ref "D32") (pin "2") (pinfunction "A_2") (pintype "unspecified"))
      (node (ref "SW32") (pin "ROW") (pinfunction "ROW_ROW") (pintype "unspecified"))
    )
    (net (code "53") (name "Net-(D33-A)") (class "Default")
      (node (ref "D33") (pin "2") (pinfunction "A_2") (pintype "unspecified"))
      (node (ref "SW33") (pin "ROW") (pinfunction "ROW_ROW") (pintype "unspecified"))
    )
    (net (code "54") (name "Net-(D34-A)") (class "Default")
      (node (ref "D34") (pin "2") (pinfunction "A_2") (pintype "unspecified"))
      (node (ref "SW34") (pin "ROW") (pinfunction "ROW_ROW") (pintype "unspecified"))
    )
    (net (code "55") (name "Net-(D35-A)") (class "Default")
      (node (ref "D35") (pin "2") (pinfunction "A_2") (pintype "unspecified"))
      (node (ref "SW35") (pin "ROW") (pinfunction "ROW_ROW") (pintype "unspecified"))
    )
    (net (code "56") (name "Net-(D36-A)") (class "Default")
      (node (ref "D36") (pin "2") (pinfunction "A_2") (pintype "unspecified"))
      (node (ref "SW36") (pin "ROW") (pinfunction "ROW_ROW") (pintype "unspecified"))
    )
    (net (code "57") (name "Net-(D37-A)") (class "Default")
      (node (ref "D37") (pin "2") (pinfunction "A_2") (pintype "unspecified"))
      (node (ref "SW37") (pin "ROW") (pinfunction "ROW_ROW") (pintype "unspecified"))
    )
    (net (code "58") (name "Net-(D38-A)") (class "Default")
      (node (ref "D38") (pin "2") (pinfunction "A_2") (pintype "unspecified"))
      (node (ref "SW38") (pin "ROW") (pinfunction "ROW_ROW") (pintype "unspecified"))
    )
    (net (code "59") (name "Net-(D39-A)") (class "Default")
      (node (ref "D39") (pin "2") (pinfunction "A_2") (pintype "unspecified"))
      (node (ref "SW39") (pin "ROW") (pinfunction "ROW_ROW") (pintype "unspecified"))
    )
    (net (code "60") (name "Net-(D40-A)") (class "Default")
      (node (ref "D40") (pin "2") (pinfunction "A_2") (pintype "unspecified"))
      (node (ref "SW40") (pin "ROW") (pinfunction "ROW_ROW") (pintype "unspecified"))
    )
    (net (code "61") (name "Net-(D41-A)") (class "Default")
      (node (ref "D41") (pin "2") (pinfunction "A_2") (pintype "unspecified"))
      (node (ref "SW41") (pin "ROW") (pinfunction "ROW_ROW") (pintype "unspecified"))
    )
    (net (code "62") (name "Net-(D42-A)") (class "Default")
      (node (ref "D42") (pin "2") (pinfunction "A_2") (pintype "unspecified"))
      (node (ref "SW42") (pin "ROW") (pinfunction "ROW_ROW") (pintype "unspecified"))
    )
    (net (code "63") (name "Net-(D43-A)") (class "Default")
      (node (ref "D43") (pin "2") (pinfunction "A_2") (pintype "unspecified"))
      (node (ref "SW43") (pin "ROW") (pinfunction "ROW_ROW") (pintype "unspecified"))
    )
    (net (code "64") (name "Net-(D44-A)") (class "Default")
      (node (ref "D44") (pin "2") (pinfunction "A_2") (pintype "unspecified"))
      (node (ref "SW44") (pin "ROW") (pinfunction "ROW_ROW") (pintype "unspecified"))
    )
    (net (code "65") (name "Net-(D45-A)") (class "Default")
      (node (ref "D45") (pin "2") (pinfunction "A_2") (pintype "unspecified"))
      (node (ref "SW45") (pin "ROW") (pinfunction "ROW_ROW") (pintype "unspecified"))
    )
    (net (code "66") (name "Net-(D46-A)") (class "Default")
      (node (ref "D46") (pin "2") (pinfunction "A_2") (pintype "unspecified"))
      (node (ref "SW46") (pin "ROW") (pinfunction "ROW_ROW") (pintype "unspecified"))
    )
    (net (code "67") (name "Net-(D47-A)") (class "Default")
      (node (ref "D47") (pin "2") (pinfunction "A_2") (pintype "unspecified"))
      (node (ref "SW47") (pin "ROW") (pinfunction "ROW_ROW") (pintype "unspecified"))
    )
    (net (code "68") (name "Net-(D48-A)") (class "Default")
      (node (ref "D48") (pin "2") (pinfunction "A_2") (pintype "unspecified"))
      (node (ref "SW48") (pin "ROW") (pinfunction "ROW_ROW") (pintype "unspecified"))
    )
    (net (code "69") (name "Net-(D49-A)") (class "Default")
      (node (ref "D49") (pin "2") (pinfunction "A_2") (pintype "unspecified"))
      (node (ref "SW49") (pin "ROW") (pinfunction "ROW_ROW") (pintype "unspecified"))
    )
    (net (code "70") (name "Net-(D50-A)") (class "Default")
      (node (ref "D50") (pin "2") (pinfunction "A_2") (pintype "unspecified"))
      (node (ref "SW50") (pin "ROW") (pinfunction "ROW_ROW") (pintype "unspecified"))
    )
    (net (code "71") (name "Net-(D51-A)") (class "Default")
      (node (ref "D51") (pin "2") (pinfunction "A_2") (pintype "unspecified"))
      (node (ref "SW51") (pin "ROW") (pinfunction "ROW_ROW") (pintype "unspecified"))
    )
    (net (code "72") (name "Net-(D52-A)") (class "Default")
      (node (ref "D52") (pin "2") (pinfunction "A_2") (pintype "unspecified"))
      (node (ref "SW52") (pin "ROW") (pinfunction "ROW_ROW") (pintype "unspecified"))
    )
    (net (code "73") (name "Net-(D53-A)") (class "Default")
      (node (ref "D53") (pin "2") (pinfunction "A_2") (pintype "unspecified"))
      (node (ref "SW53") (pin "ROW") (pinfunction "ROW_ROW") (pintype "unspecified"))
    )
    (net (code "74") (name "Net-(D54-A)") (class "Default")
      (node (ref "D54") (pin "2") (pinfunction "A_2") (pintype "unspecified"))
      (node (ref "SW54") (pin "ROW") (pinfunction "ROW_ROW") (pintype "unspecified"))
    )
    (net (code "75") (name "Net-(D55-A)") (class "Default")
      (node (ref "D55") (pin "2") (pinfunction "A_2") (pintype "unspecified"))
      (node (ref "SW55") (pin "ROW") (pinfunction "ROW_ROW") (pintype "unspecified"))
    )
    (net (code "76") (name "Net-(D56-A)") (class "Default")
      (node (ref "D56") (pin "2") (pinfunction "A_2") (pintype "unspecified"))
      (node (ref "SW56") (pin "ROW") (pinfunction "ROW_ROW") (pintype "unspecified"))
    )
    (net (code "77") (name "Net-(D57-A)") (class "Default")
      (node (ref "D57") (pin "2") (pinfunction "A_2") (pintype "unspecified"))
      (node (ref "SW57") (pin "ROW") (pinfunction "ROW_ROW") (pintype "unspecified"))
    )
    (net (code "78") (name "Net-(D58-A)") (class "Default")
      (node (ref "D58") (pin "2") (pinfunction "A_2") (pintype "unspecified"))
      (node (ref "SW58") (pin "ROW") (pinfunction "ROW_ROW") (pintype "unspecified"))
    )
    (net (code "79") (name "Net-(D59-A)") (class "Default")
      (node (ref "D59") (pin "2") (pinfunction "A_2") (pintype "unspecified"))
      (node (ref "SW59") (pin "ROW") (pinfunction "ROW_ROW") (pintype "unspecified"))
    )
    (net (code "80") (name "Net-(D60-A)") (class "Default")
      (node (ref "D60") (pin "2") (pinfunction "A_2") (pintype "unspecified"))
      (node (ref "SW60") (pin "ROW") (pinfunction "ROW_ROW") (pintype "unspecified"))
    )
    (net (code "81") (name "Net-(D61-A)") (class "Default")
      (node (ref "D61") (pin "2") (pinfunction "A_2") (pintype "unspecified"))
      (node (ref "SW61") (pin "ROW") (pinfunction "ROW_ROW") (pintype "unspecified"))
    )
    (net (code "82") (name "Net-(D62-A)") (class "Default")
      (node (ref "D62") (pin "2") (pinfunction "A_2") (pintype "unspecified"))
      (node (ref "SW62") (pin "ROW") (pinfunction "ROW_ROW") (pintype "unspecified"))
    )
    (net (code "83") (name "Net-(D63-A)") (class "Default")
      (node (ref "D63") (pin "2") (pinfunction "A_2") (pintype "unspecified"))
      (node (ref "SW63") (pin "ROW") (pinfunction "ROW_ROW") (pintype "unspecified"))
    )
    (net (code "84") (name "Net-(D64-A)") (class "Default")
      (node (ref "D64") (pin "2") (pinfunction "A_2") (pintype "unspecified"))
      (node (ref "SW64") (pin "ROW") (pinfunction "ROW_ROW") (pintype "unspecified"))
    )
    (net (code "85") (name "Net-(D65-A)") (class "Default")
      (node (ref "D65") (pin "2") (pinfunction "A_2") (pintype "unspecified"))
      (node (ref "SW65") (pin "ROW") (pinfunction "ROW_ROW") (pintype "unspecified"))
    )
    (net (code "86") (name "Net-(D66-A)") (class "Default")
      (node (ref "D66") (pin "2") (pinfunction "A_2") (pintype "unspecified"))
      (node (ref "SW66") (pin "ROW") (pinfunction "ROW_ROW") (pintype "unspecified"))
    )
    (net (code "87") (name "Net-(D67-A)") (class "Default")
      (node (ref "D67") (pin "2") (pinfunction "A_2") (pintype "unspecified"))
      (node (ref "SW67") (pin "ROW") (pinfunction "ROW_ROW") (pintype "unspecified"))
    )
    (net (code "88") (name "Net-(SW1-PadDOUT)") (class "Default")
      (node (ref "SW1") (pin "DOUT") (pinfunction "DOUT_DOUT") (pintype "unspecified"))
      (node (ref "SW2") (pin "DIN") (pinfunction "DIN_DIN") (pintype "unspecified"))
    )
    (net (code "89") (name "Net-(SW2-PadDOUT)") (class "Default")
      (node (ref "SW2") (pin "DOUT") (pinfunction "DOUT_DOUT") (pintype "unspecified"))
      (node (ref "SW4") (pin "DIN") (pinfunction "DIN_DIN") (pintype "unspecified"))
    )
    (net (code "90") (name "Net-(SW3-PadDIN)") (class "Default")
      (node (ref "SW3") (pin "DIN") (pinfunction "DIN_DIN") (pintype "unspecified"))
      (node (ref "SW4") (pin "DOUT") (pinfunction "DOUT_DOUT") (pintype "unspecified"))
    )
    (net (code "91") (name "Net-(SW3-PadDOUT)") (class "Default")
      (node (ref "SW3") (pin "DOUT") (pinfunction "DOUT_DOUT") (pintype "unspecified"))
      (node (ref "SW6") (pin "DIN") (pinfunction "DIN_DIN") (pintype "unspecified"))
    )
    (net (code "92") (name "Net-(SW5-PadDIN)") (class "Default")
      (node (ref "SW5") (pin "DIN") (pinfunction "DIN_DIN") (pintype "unspecified"))
      (node (ref "SW6") (pin "DOUT") (pinfunction "DOUT_DOUT") (pintype "unspecified"))
    )
    (net (code "93") (name "Net-(SW5-PadDOUT)") (class "Default")
      (node (ref "SW5") (pin "DOUT") (pinfunction "DOUT_DOUT") (pintype "unspecified"))
      (node (ref "SW8") (pin "DIN") (pinfunction "DIN_DIN") (pintype "unspecified"))
    )
    (net (code "94") (name "Net-(SW7-PadDIN)") (class "Default")
      (node (ref "SW7") (pin "DIN") (pinfunction "DIN_DIN") (pintype "unspecified"))
      (node (ref "SW8") (pin "DOUT") (pinfunction "DOUT_DOUT") (pintype "unspecified"))
    )
    (net (code "95") (name "Net-(SW10-PadDIN)") (class "Default")
      (node (ref "SW10") (pin "DIN") (pinfunction "DIN_DIN") (pintype "unspecified"))
      (node (ref "SW9") (pin "DOUT") (pinfunction "DOUT_DOUT") (pintype "unspecified"))
    )
    (net (code "96") (name "Net-(SW11-PadDIN)") (class "Default")
      (node (ref "SW11") (pin "DIN") (pinfunction "DIN_DIN") (pintype "unspecified"))
      (node (ref "SW14") (pin "DOUT") (pinfunction "DOUT_DOUT") (pintype "unspecified"))
    )
    (net (code "97") (name "Net-(SW11-PadDOUT)") (class "Default")
      (node (ref "SW11") (pin "DOUT") (pinfunction "DOUT_DOUT") (pintype "unspecified"))
      (node (ref "SW12") (pin "DIN") (pinfunction "DIN_DIN") (pintype "unspecified"))
    )
    (net (code "98") (name "Net-(SW12-PadDOUT)") (class "Default")
      (node (ref "SW12") (pin "DOUT") (pinfunction "DOUT_DOUT") (pintype "unspecified"))
      (node (ref "SW9") (pin "DIN") (pinfunction "DIN_DIN") (pintype "unspecified"))
    )
    (net (code "99") (name "Net-(SW13-PadDIN)") (class "Default")
      (node (ref "SW13") (pin "DIN") (pinfunction "DIN_DIN") (pintype "unspecified"))
      (node (ref "SW15") (pin "DOUT") (pinfunction "DOUT_DOUT") (pintype "unspecified"))
    )
    (net (code "100") (name "Net-(SW13-PadDOUT)") (class "Default")
      (node (ref "SW13") (pin "DOUT") (pinfunction "DOUT_DOUT") (pintype "unspecified"))
      (node (ref "SW14") (pin "DIN") (pinfunction "DIN_DIN") (pintype "unspecified"))
    )
    (net (code "101") (name "Net-(SW15-PadDIN)") (class "Default")
      (node (ref "SW15") (pin "DIN") (pinfunction "DIN_DIN") (pintype "unspecified"))
      (node (ref "SW7") (pin "DOUT") (pinfunction "DOUT_DOUT") (pintype "unspecified"))
    )
    (net (code "102") (name "Net-(SW16-PadDIN)") (class "Default")
      (node (ref "SW16") (pin "DIN") (pinfunction "DIN_DIN") (pintype "unspecified"))
      (node (ref "SW19") (pin "DOUT") (pinfunction "DOUT_DOUT") (pintype "unspecified"))
    )
    (net (code "103") (name "Net-(SW16-PadDOUT)") (class "Default")
      (node (ref "SW16") (pin "DOUT") (pinfunction "DOUT_DOUT") (pintype "unspecified"))
      (node (ref "SW17") (pin "DIN") (pinfunction "DIN_DIN") (pintype "unspecified"))
    )
    (net (code "104") (name "Net-(SW18-PadDIN)") (class "Default")
      (node (ref "SW18") (pin "DIN") (pinfunction "DIN_DIN") (pintype "unspecified"))
      (node (ref "SW21") (pin "DOUT") (pinfunction "DOUT_DOUT") (pintype "unspecified"))
    )
    (net (code "105") (name "Net-(SW18-PadDOUT)") (class "Default")
      (node (ref "SW18") (pin "DOUT") (pinfunction "DOUT_DOUT") (pintype "unspecified"))
      (node (ref "SW19") (pin "DIN") (pinfunction "DIN_DIN") (pintype "unspecified"))
    )
    (net (code "106") (name "Net-(SW20-PadDIN)") (class "Default")
      (node (ref "SW20") (pin "DIN") (pinfunction "DIN_DIN") (pintype "unspecified"))
      (node (ref "SW22") (pin "DOUT") (pinfunction "DOUT_DOUT") (pintype "unspecified"))
    )
    (net (code "107") (name "Net-(SW20-PadDOUT)") (class "Default")
      (node (ref "SW20") (pin "DOUT") (pinfunction "DOUT_DOUT") (pintype "unspecified"))
      (node (ref "SW21") (pin "DIN") (pinfunction "DIN_DIN") (pintype "unspecified"))
    )
    (net (code "108") (name "Net-(SW22-PadDIN)") (class "Default")
      (node (ref "SW22") (pin "DIN") (pinfunction "DIN_DIN") (pintype "unspecified"))
      (node (ref "SW24") (pin "DOUT") (pinfunction "DOUT_DOUT") (pintype "unspecified"))
    )
    (net (code "109") (name "Net-(SW23-PadDIN)") (class "Default")
      (node (ref "SW23") (pin "DIN") (pinfunction "DIN_DIN") (pintype "unspecified"))
      (node (ref "SW26") (pin "DOUT") (pinfunction "DOUT_DOUT") (pintype "unspecified"))
    )
    (net (code "110") (name "Net-(SW23-PadDOUT)") (class "Default")
      (node (ref "SW23") (pin "DOUT") (pinfunction "DOUT_DOUT") (pintype "unspecified"))
      (node (ref "SW24") (pin "DIN") (pinfunction "DIN_DIN") (pintype "unspecified"))
    )
    (net (code "111") (name "Net-(SW25-PadDIN)") (class "Default")
      (node (ref "SW25") (pin "DIN") (pinfunction "DIN_DIN") (pintype "unspecified"))
      (node (ref "SW28") (pin "DOUT") (pinfunction "DOUT_DOUT") (pintype "unspecified"))
    )
    (net (code "112") (name "Net-(SW25-PadDOUT)") (class "Default")
      (node (ref "SW25") (pin "DOUT") (pinfunction "DOUT_DOUT") (pintype "unspecified"))
      (node (ref "SW26") (pin "DIN") (pinfunction "DIN_DIN") (pintype "unspecified"))
    )
    (net (code "113") (name "Net-(SW27-PadDIN)") (class "Default")
      (node (ref "SW27") (pin "DIN") (pinfunction "DIN_DIN") (pintype "unspecified"))
      (node (ref "SW29") (pin "DOUT") (pinfunction "DOUT_DOUT") (pintype "unspecified"))
    )
    (net (code "114") (name "Net-(SW27-PadDOUT)") (class "Default")
      (node (ref "SW27") (pin "DOUT") (pinfunction "DOUT_DOUT") (pintype "unspecified"))
      (node (ref "SW28") (pin "DIN") (pinfunction "DIN_DIN") (pintype "unspecified"))
    )
    (net (code "115") (name "Net-(SW29-PadDIN)") (class "Default")
      (node (ref "SW29") (pin "DIN") (pinfunction "DIN_DIN") (pintype "unspecified"))
      (node (ref "SW30") (pin "DOUT") (pinfunction "DOUT_DOUT") (pintype "unspecified"))
    )
    (net (code "116") (name "Net-(SW31-PadDOUT)") (class "Default")
      (node (ref "SW31") (pin "DOUT") (pinfunction "DOUT_DOUT") (pintype "unspecified"))
      (node (ref "SW32") (pin "DIN") (pinfunction "DIN_DIN") (pintype "unspecified"))
    )
    (net (code "117") (name "Net-(SW32-PadDOUT)") (class "Default")
      (node (ref "SW32") (pin "DOUT") (pinfunction "DOUT_DOUT") (pintype "unspecified"))
      (node (ref "SW47") (pin "DIN") (pinfunction "DIN_DIN") (pintype "unspecified"))
    )
    (net (code "118") (name "Net-(SW33-PadDIN)") (class "Default")
      (node (ref "SW33") (pin "DIN") (pinfunction "DIN_DIN") (pintype "unspecified"))
      (node (ref "SW36") (pin "DOUT") (pinfunction "DOUT_DOUT") (pintype "unspecified"))
    )
    (net (code "119") (name "Net-(SW33-PadDOUT)") (class "Default")
      (node (ref "SW33") (pin "DOUT") (pinfunction "DOUT_DOUT") (pintype "unspecified"))
      (node (ref "SW34") (pin "DIN") (pinfunction "DIN_DIN") (pintype "unspecified"))
    )
    (net (code "120") (name "Net-(SW35-PadDIN)") (class "Default")
      (node (ref "SW35") (pin "DIN") (pinfunction "DIN_DIN") (pintype "unspecified"))
      (node (ref "SW37") (pin "DOUT") (pinfunction "DOUT_DOUT") (pintype "unspecified"))
    )
    (net (code "121") (name "Net-(SW35-PadDOUT)") (class "Default")
      (node (ref "SW35") (pin "DOUT") (pinfunction "DOUT_DOUT") (pintype "unspecified"))
      (node (ref "SW36") (pin "DIN") (pinfunction "DIN_DIN") (pintype "unspecified"))
    )
    (net (code "122") (name "Net-(SW37-PadDIN)") (class "Default")
      (node (ref "SW37") (pin "DIN") (pinfunction "DIN_DIN") (pintype "unspecified"))
      (node (ref "SW39") (pin "DOUT") (pinfunction "DOUT_DOUT") (pintype "unspecified"))
    )
    (net (code "123") (name "Net-(SW38-PadDIN)") (class "Default")
      (node (ref "SW38") (pin "DIN") (pinfunction "DIN_DIN") (pintype "unspecified"))
      (node (ref "SW41") (pin "DOUT") (pinfunction "DOUT_DOUT") (pintype "unspecified"))
    )
    (net (code "124") (name "Net-(SW38-PadDOUT)") (class "Default")
      (node (ref "SW38") (pin "DOUT") (pinfunction "DOUT_DOUT") (pintype "unspecified"))
      (node (ref "SW39") (pin "DIN") (pinfunction "DIN_DIN") (pintype "unspecified"))
    )
    (net (code "125") (name "Net-(SW40-PadDIN)") (class "Default")
      (node (ref "SW40") (pin "DIN") (pinfunction "DIN_DIN") (pintype "unspecified"))
      (node (ref "SW43") (pin "DOUT") (pinfunction "DOUT_DOUT") (pintype "unspecified"))
    )
    (net (code "126") (name "Net-(SW40-PadDOUT)") (class "Default")
      (node (ref "SW40") (pin "DOUT") (pinfunction "DOUT_DOUT") (pintype "unspecified"))
      (node (ref "SW41") (pin "DIN") (pinfunction "DIN_DIN") (pintype "unspecified"))
    )
    (net (code "127") (name "Net-(SW42-PadDIN)") (class "Default")
      (node (ref "SW42") (pin "DIN") (pinfunction "DIN_DIN") (pintype "unspecified"))
      (node (ref "SW44") (pin "DOUT") (pinfunction "DOUT_DOUT") (pintype "unspecified"))
    )
    (net (code "128") (name "Net-(SW42-PadDOUT)") (class "Default")
      (node (ref "SW42") (pin "DOUT") (pinfunction "DOUT_DOUT") (pintype "unspecified"))
      (node (ref "SW43") (pin "DIN") (pinfunction "DIN_DIN") (pintype "unspecified"))
    )
    (net (code "129") (name "Net-(SW44-PadDIN)") (class "Default")
      (node (ref "SW44") (pin "DIN") (pinfunction "DIN_DIN") (pintype "unspecified"))
      (node (ref "SW45") (pin "DOUT") (pinfunction "DOUT_DOUT") (pintype "unspecified"))
    )
    (net (code "130") (name "Net-(SW46-PadDIN)") (class "Default")
      (node (ref "SW46") (pin "DIN") (pinfunction "DIN_DIN") (pintype "unspecified"))
      (node (ref "SW47") (pin "DOUT") (pinfunction "DOUT_DOUT") (pintype "unspecified"))
    )
    (net (code "131") (name "Net-(SW46-PadDOUT)") (class "Default")
      (node (ref "SW46") (pin "DOUT") (pinfunction "DOUT_DOUT") (pintype "unspecified"))
      (node (ref "SW49") (pin "DIN") (pinfunction "DIN_DIN") (pintype "unspecified"))
    )
    (net (code "132") (name "Net-(SW48-PadDIN)") (class "Default")
      (node (ref "SW48") (pin "DIN") (pinfunction "DIN_DIN") (pintype "unspecified"))
      (node (ref "SW49") (pin "DOUT") (pinfunction "DOUT_DOUT") (pintype "unspecified"))
    )
    (net (code "133") (name "Net-(SW48-PadDOUT)") (class "Default")
      (node (ref "SW48") (pin "DOUT") (pinfunction "DOUT_DOUT") (pintype "unspecified"))
      (node (ref "SW51") (pin "DIN") (pinfunction "DIN_DIN") (pintype "unspecified"))
    )
    (net (code "134") (name "Net-(SW50-PadDIN)") (class "Default")
      (node (ref "SW50") (pin "DIN") (pinfunction "DIN_DIN") (pintype "unspecified"))
      (node (ref "SW51") (pin "DOUT") (pinfunction "DOUT_DOUT") (pintype "unspecified"))
    )
    (net (code "135") (name "Net-(SW50-PadDOUT)") (class "Default")
      (node (ref "SW50") (pin "DOUT") (pinfunction "DOUT_DOUT") (pintype "unspecified"))
      (node (ref "SW52") (pin "DIN") (pinfunction "DIN_DIN") (pintype "unspecified"))
    )
    (net (code "136") (name "Net-(SW52-PadDOUT)") (class "Default")
      (node (ref "SW52") (pin "DOUT") (pinfunction "DOUT_DOUT") (pintype "unspecified"))
      (node (ref "SW54") (pin "DIN") (pinfunction "DIN_DIN") (pintype "unspecified"))
    )
    (net (code "137") (name "Net-(SW53-PadDIN)") (class "Default")
      (node (ref "SW53") (pin "DIN") (pinfunction "DIN_DIN") (pintype "unspecified"))
      (node (ref "SW54") (pin "DOUT") (pinfunction "DOUT_DOUT") (pintype "unspecified"))
    )
    (net (code "138") (name "Net-(SW53-PadDOUT)") (class "Default")
      (node (ref "SW53") (pin "DOUT") (pinfunction "DOUT_DOUT") (pintype "unspecified"))
      (node (ref "SW56") (pin "DIN") (pinfunction "DIN_DIN") (pintype "unspecified"))
    )
    (net (code "139") (name "Net-(SW55-PadDIN)") (class "Default")
      (node (ref "SW55") (pin "DIN") (pinfunction "DIN_DIN") (pintype "unspecified"))
      (node (ref "SW56") (pin "DOUT") (pinfunction "DOUT_DOUT") (pintype "unspecified"))
    )
    (net (code "140") (name "Net-(SW57-PadDOUT)") (class "Default")
      (node (ref "SW57") (pin "DOUT") (pinfunction "DOUT_DOUT") (pintype "unspecified"))
      (node (ref "SW58") (pin "DIN") (pinfunction "DIN_DIN") (pintype "unspecified"))
    )
    (net (code "141") (name "Net-(SW58-PadDOUT)") (class "Default")
      (node (ref "SW58") (pin "DOUT") (pinfunction "DOUT_DOUT") (pintype "unspecified"))
      (node (ref "SW60") (pin "DIN") (pinfunction "DIN_DIN") (pintype "unspecified"))
    )
    (net (code "142") (name "Net-(SW59-PadDIN)") (class "Default")
      (node (ref "SW59") (pin "DIN") (pinfunction "DIN_DIN") (pintype "unspecified"))
      (node (ref "SW60") (pin "DOUT") (pinfunction "DOUT_DOUT") (pintype "unspecified"))
    )
    (net (code "143") (name "Net-(SW59-PadDOUT)") (class "Default")
      (node (ref "SW59") (pin "DOUT") (pinfunction "DOUT_DOUT") (pintype "unspecified"))
      (node (ref "SW62") (pin "DIN") (pinfunction "DIN_DIN") (pintype "unspecified"))
    )
    (net (code "144") (name "Net-(SW61-PadDIN)") (class "Default")
      (node (ref "SW61") (pin "DIN") (pinfunction "DIN_DIN") (pintype "unspecified"))
      (node (ref "SW62") (pin "DOUT") (pinfunction "DOUT_DOUT") (pintype "unspecified"))
    )
    (net (code "145") (name "Net-(SW61-PadDOUT)") (class "Default")
      (node (ref "SW61") (pin "DOUT") (pinfunction "DOUT_DOUT") (pintype "unspecified"))
      (node (ref "SW64") (pin "DIN") (pinfunction "DIN_DIN") (pintype "unspecified"))
    )
    (net (code "146") (name "Net-(SW63-PadDIN)") (class "Default")
      (node (ref "SW63") (pin "DIN") (pinfunction "DIN_DIN") (pintype "unspecified"))
      (node (ref "SW64") (pin "DOUT") (pinfunction "DOUT_DOUT") (pintype "unspecified"))
    )
    (net (code "147") (name "Net-(SW63-PadDOUT)") (class "Default")
      (node (ref "SW63") (pin "DOUT") (pinfunction "DOUT_DOUT") (pintype "unspecified"))
      (node (ref "SW65") (pin "DIN") (pinfunction "DIN_DIN") (pintype "unspecified"))
    )
    (net (code "148") (name "Net-(SW65-PadDOUT)") (class "Default")
      (node (ref "SW65") (pin "DOUT") (pinfunction "DOUT_DOUT") (pintype "unspecified"))
      (node (ref "SW67") (pin "DIN") (pinfunction "DIN_DIN") (pintype "unspecified"))
    )
    (net (code "149") (name "Net-(SW66-PadDIN)") (class "Default")
      (node (ref "SW66") (pin "DIN") (pinfunction "DIN_DIN") (pintype "unspecified"))
      (node (ref "SW67") (pin "DOUT") (pinfunction "DOUT_DOUT") (pintype "unspecified"))
    )
    (net (code "150") (name "Net-(U1-PE2_(HWB#))") (class "Default")
      (node (ref "R1") (pin "1") (pinfunction "1_1") (pintype "unspecified"))
      (node (ref "U1") (pin "33") (pinfunction "PE2_(HWB#)_33") (pintype "bidirectional"))
    )
    (net (code "151") (name "Net-(U1-RESET#)") (class "Default")
      (node (ref "KEY1") (pin "2") (pinfunction "2_2") (pintype "input"))
      (node (ref "R2") (pin "2") (pinfunction "2_2") (pintype "unspecified"))
      (node (ref "U1") (pin "13") (pinfunction "RESET#_13") (pintype "unspecified"))
    )
    (net (code "152") (name "Net-(U1-UCap)") (class "Default")
      (node (ref "C1") (pin "1") (pinfunction "1_1") (pintype "unspecified"))
      (node (ref "U1") (pin "6") (pinfunction "UCap_6") (pintype "unspecified"))
    )
    (net (code "153") (name "Net-(U1-XTAL1)") (class "Default")
      (node (ref "C3") (pin "1") (pinfunction "1_1") (pintype "unspecified"))
      (node (ref "U1") (pin "17") (pinfunction "XTAL1_17") (pintype "unspecified"))
      (node (ref "X1") (pin "2") (pinfunction "OSC2_2") (pintype "input"))
    )
    (net (code "154") (name "Net-(U1-XTAL2)") (class "Default")
      (node (ref "C2") (pin "1") (pinfunction "1_1") (pintype "unspecified"))
      (node (ref "U1") (pin "16") (pinfunction "XTAL2_16") (pintype "output"))
      (node (ref "X1") (pin "1") (pinfunction "OSC1_1") (pintype "input"))
    )
    (net (code "155") (name "Net-(U2-DIN)") (class "Default")
      (node (ref "SW66") (pin "DOUT") (pinfunction "DOUT_DOUT") (pintype "unspecified"))
      (node (ref "U2") (pin "4") (pinfunction "DIN_4") (pintype "unspecified"))
    )
    (net (code "156") (name "Net-(U2-DOUT)") (class "Default")
      (node (ref "U2") (pin "2") (pinfunction "DOUT_2") (pintype "unspecified"))
      (node (ref "U3") (pin "4") (pinfunction "DIN_4") (pintype "unspecified"))
    )
    (net (code "157") (name "Net-(U3-DOUT)") (class "Default")
      (node (ref "U3") (pin "2") (pinfunction "DOUT_2") (pintype "unspecified"))
      (node (ref "U4") (pin "4") (pinfunction "DIN_4") (pintype "unspecified"))
    )
    (net (code "158") (name "Net-(U4-DOUT)") (class "Default")
      (node (ref "U4") (pin "2") (pinfunction "DOUT_2") (pintype "unspecified"))
      (node (ref "U5") (pin "4") (pinfunction "DIN_4") (pintype "unspecified"))
    )
    (net (code "159") (name "Net-(U5-DOUT)") (class "Default")
      (node (ref "U5") (pin "2") (pinfunction "DOUT_2") (pintype "unspecified"))
      (node (ref "U6") (pin "4") (pinfunction "DIN_4") (pintype "unspecified"))
    )
    (net (code "160") (name "Net-(U6-DOUT)") (class "Default")
      (node (ref "U6") (pin "2") (pinfunction "DOUT_2") (pintype "unspecified"))
      (node (ref "U9") (pin "4") (pinfunction "DIN_4") (pintype "unspecified"))
    )
    (net (code "161") (name "Net-(U7-DIN)") (class "Default")
      (node (ref "U7") (pin "4") (pinfunction "DIN_4") (pintype "unspecified"))
      (node (ref "U8") (pin "2") (pinfunction "DOUT_2") (pintype "unspecified"))
    )
    (net (code "162") (name "Net-(U8-DIN)") (class "Default")
      (node (ref "U8") (pin "4") (pinfunction "DIN_4") (pintype "unspecified"))
      (node (ref "U9") (pin "2") (pinfunction "DOUT_2") (pintype "unspecified"))
    )
    (net (code "163") (name "Net-(USBC1-DN1)") (class "Default")
      (node (ref "R3") (pin "2") (pinfunction "2_2") (pintype "input"))
      (node (ref "USBC1") (pin "A7") (pinfunction "DN1_A7") (pintype "unspecified"))
      (node (ref "USBC1") (pin "B7") (pinfunction "DN2_B7") (pintype "unspecified"))
    )
    (net (code "164") (name "Net-(USBC1-DP1)") (class "Default")
      (node (ref "R4") (pin "1") (pinfunction "1_1") (pintype "input"))
      (node (ref "USBC1") (pin "A6") (pinfunction "DP1_A6") (pintype "unspecified"))
      (node (ref "USBC1") (pin "B6") (pinfunction "DP2_B6") (pintype "unspecified"))
    )
    (net (code "165") (name "RGB") (class "Default")
      (node (ref "SW1") (pin "DIN") (pinfunction "DIN_DIN") (pintype "unspecified"))
      (node (ref "U1") (pin "8") (pinfunction "PB0(SS/PCINT0)_8") (pintype "bidirectional"))
    )
    (net (code "166") (name "RGB1") (class "Default")
      (node (ref "SW10") (pin "DOUT") (pinfunction "DOUT_DOUT") (pintype "unspecified"))
      (node (ref "SW30") (pin "DIN") (pinfunction "DIN_DIN") (pintype "unspecified"))
    )
    (net (code "167") (name "RGB2") (class "Default")
      (node (ref "SW17") (pin "DOUT") (pinfunction "DOUT_DOUT") (pintype "unspecified"))
      (node (ref "SW45") (pin "DIN") (pinfunction "DIN_DIN") (pintype "unspecified"))
    )
    (net (code "168") (name "RGB3") (class "Default")
      (node (ref "SW31") (pin "DIN") (pinfunction "DIN_DIN") (pintype "unspecified"))
      (node (ref "SW34") (pin "DOUT") (pinfunction "DOUT_DOUT") (pintype "unspecified"))
    )
    (net (code "169") (name "RGB4") (class "Default")
      (node (ref "SW55") (pin "DOUT") (pinfunction "DOUT_DOUT") (pintype "unspecified"))
      (node (ref "SW57") (pin "DIN") (pinfunction "DIN_DIN") (pintype "unspecified"))
    )
    (net (code "170") (name "ROW0") (class "Default")
      (node (ref "D1") (pin "1") (pinfunction "K_1") (pintype "unspecified"))
      (node (ref "D10") (pin "1") (pinfunction "K_1") (pintype "unspecified"))
      (node (ref "D11") (pin "1") (pinfunction "K_1") (pintype "unspecified"))
      (node (ref "D12") (pin "1") (pinfunction "K_1") (pintype "unspecified"))
      (node (ref "D13") (pin "1") (pinfunction "K_1") (pintype "unspecified"))
      (node (ref "D14") (pin "1") (pinfunction "K_1") (pintype "unspecified"))
      (node (ref "D15") (pin "1") (pinfunction "K_1") (pintype "unspecified"))
      (node (ref "D2") (pin "1") (pinfunction "K_1") (pintype "unspecified"))
      (node (ref "D3") (pin "1") (pinfunction "K_1") (pintype "unspecified"))
      (node (ref "D4") (pin "1") (pinfunction "K_1") (pintype "unspecified"))
      (node (ref "D5") (pin "1") (pinfunction "K_1") (pintype "unspecified"))
      (node (ref "D6") (pin "1") (pinfunction "K_1") (pintype "unspecified"))
      (node (ref "D7") (pin "1") (pinfunction "K_1") (pintype "unspecified"))
      (node (ref "D8") (pin "1") (pinfunction "K_1") (pintype "unspecified"))
      (node (ref "D9") (pin "1") (pinfunction "K_1") (pintype "unspecified"))
      (node (ref "SW68") (pin "E") (pinfunction "E_E") (pintype "unspecified"))
      (node (ref "U1") (pin "12") (pinfunction "PB7(PCINT7/OC0A/OC1C/RTS#)_12") (pintype "bidirectional"))
    )
    (net (code "171") (name "ROW1") (class "Default")
      (node (ref "D16") (pin "1") (pinfunction "K_1") (pintype "unspecified"))
      (node (ref "D17") (pin "1") (pinfunction "K_1") (pintype "unspecified"))
      (node (ref "D18") (pin "1") (pinfunction "K_1") (pintype "unspecified"))
      (node (ref "D19") (pin "1") (pinfunction "K_1") (pintype "unspecified"))
      (node (ref "D20") (pin "1") (pinfunction "K_1") (pintype "unspecified"))
      (node (ref "D21") (pin "1") (pinfunction "K_1") (pintype "unspecified"))
      (node (ref "D22") (pin "1") (pinfunction "K_1") (pintype "unspecified"))
      (node (ref "D23") (pin "1") (pinfunction "K_1") (pintype "unspecified"))
      (node (ref "D24") (pin "1") (pinfunction "K_1") (pintype "unspecified"))
      (node (ref "D25") (pin "1") (pinfunction "K_1") (pintype "unspecified"))
      (node (ref "D26") (pin "1") (pinfunction "K_1") (pintype "unspecified"))
      (node (ref "D27") (pin "1") (pinfunction "K_1") (pintype "unspecified"))
      (node (ref "D28") (pin "1") (pinfunction "K_1") (pintype "unspecified"))
      (node (ref "D29") (pin "1") (pinfunction "K_1") (pintype "unspecified"))
      (node (ref "D30") (pin "1") (pinfunction "K_1") (pintype "unspecified"))
      (node (ref "U1") (pin "18") (pinfunction "PD0_(OC0B/SCL/INT0)_18") (pintype "bidirectional"))
    )
    (net (code "172") (name "ROW2") (class "Default")
      (node (ref "D33") (pin "1") (pinfunction "K_1") (pintype "unspecified"))
      (node (ref "D34") (pin "1") (pinfunction "K_1") (pintype "unspecified"))
      (node (ref "D35") (pin "1") (pinfunction "K_1") (pintype "unspecified"))
      (node (ref "D36") (pin "1") (pinfunction "K_1") (pintype "unspecified"))
      (node (ref "D37") (pin "1") (pinfunction "K_1") (pintype "unspecified"))
      (node (ref "D38") (pin "1") (pinfunction "K_1") (pintype "unspecified"))
      (node (ref "D39") (pin "1") (pinfunction "K_1") (pintype "unspecified"))
      (node (ref "D40") (pin "1") (pinfunction "K_1") (pintype "unspecified"))
      (node (ref "D41") (pin "1") (pinfunction "K_1") (pintype "unspecified"))
      (node (ref "D42") (pin "1") (pinfunction "K_1") (pintype "unspecified"))
      (node (ref "D43") (pin "1") (pinfunction "K_1") (pintype "unspecified"))
      (node (ref "D44") (pin "1") (pinfunction "K_1") (pintype "unspecified"))
      (node (ref "D45") (pin "1") (pinfunction "K_1") (pintype "unspecified"))
      (node (ref "U1") (pin "19") (pinfunction "PD1_(SDA/INT1)_19") (pintype "bidirectional"))
    )
    (net (code "173") (name "ROW3") (class "Default")
      (node (ref "D31") (pin "1") (pinfunction "K_1") (pintype "unspecified"))
      (node (ref "D32") (pin "1") (pinfunction "K_1") (pintype "unspecified"))
      (node (ref "D46") (pin "1") (pinfunction "K_1") (pintype "unspecified"))
      (node (ref "D47") (pin "1") (pinfunction "K_1") (pintype "unspecified"))
      (node (ref "D48") (pin "1") (pinfunction "K_1") (pintype "unspecified"))
      (node (ref "D49") (pin "1") (pinfunction "K_1") (pintype "unspecified"))
      (node (ref "D50") (pin "1") (pinfunction "K_1") (pintype "unspecified"))
      (node (ref "D51") (pin "1") (pinfunction "K_1") (pintype "unspecified"))
      (node (ref "D52") (pin "1") (pinfunction "K_1") (pintype "unspecified"))
      (node (ref "D53") (pin "1") (pinfunction "K_1") (pintype "unspecified"))
      (node (ref "D54") (pin "1") (pinfunction "K_1") (pintype "unspecified"))
      (node (ref "D55") (pin "1") (pinfunction "K_1") (pintype "unspecified"))
      (node (ref "D56") (pin "1") (pinfunction "K_1") (pintype "unspecified"))
      (node (ref "U1") (pin "20") (pinfunction "PD2_(RXD1/INT2)_20") (pintype "bidirectional"))
    )
    (net (code "174") (name "ROW4") (class "Default")
      (node (ref "D57") (pin "1") (pinfunction "K_1") (pintype "unspecified"))
      (node (ref "D58") (pin "1") (pinfunction "K_1") (pintype "unspecified"))
      (node (ref "D59") (pin "1") (pinfunction "K_1") (pintype "unspecified"))
      (node (ref "D60") (pin "1") (pinfunction "K_1") (pintype "unspecified"))
      (node (ref "D61") (pin "1") (pinfunction "K_1") (pintype "unspecified"))
      (node (ref "D62") (pin "1") (pinfunction "K_1") (pintype "unspecified"))
      (node (ref "D63") (pin "1") (pinfunction "K_1") (pintype "unspecified"))
      (node (ref "D64") (pin "1") (pinfunction "K_1") (pintype "unspecified"))
      (node (ref "D65") (pin "1") (pinfunction "K_1") (pintype "unspecified"))
      (node (ref "D66") (pin "1") (pinfunction "K_1") (pintype "unspecified"))
      (node (ref "D67") (pin "1") (pinfunction "K_1") (pintype "unspecified"))
      (node (ref "U1") (pin "11") (pinfunction "PB3_(PDO/PCINT3/MISO)_11") (pintype "bidirectional"))
    )
    (net (code "175") (name "VCC") (class "Default")
      (node (ref "C10") (pin "1") (pinfunction "1_1") (pintype "unspecified"))
      (node (ref "C11") (pin "1") (pinfunction "1_1") (pintype "unspecified"))
      (node (ref "C12") (pin "1") (pinfunction "1_1") (pintype "unspecified"))
      (node (ref "C13") (pin "1") (pinfunction "1_1") (pintype "unspecified"))
      (node (ref "C14") (pin "1") (pinfunction "1_1") (pintype "unspecified"))
      (node (ref "C15") (pin "1") (pinfunction "1_1") (pintype "unspecified"))
      (node (ref "C16") (pin "1") (pinfunction "1_1") (pintype "unspecified"))
      (node (ref "C17") (pin "1") (pinfunction "1_1") (pintype "unspecified"))
      (node (ref "C18") (pin "1") (pinfunction "1_1") (pintype "unspecified"))
      (node (ref "C19") (pin "1") (pinfunction "1_1") (pintype "unspecified"))
      (node (ref "C20") (pin "1") (pinfunction "1_1") (pintype "unspecified"))
      (node (ref "C21") (pin "1") (pinfunction "1_1") (pintype "unspecified"))
      (node (ref "C22") (pin "1") (pinfunction "1_1") (pintype "unspecified"))
      (node (ref "C23") (pin "1") (pinfunction "1_1") (pintype "unspecified"))
      (node (ref "C24") (pin "1") (pinfunction "1_1") (pintype "unspecified"))
      (node (ref "C25") (pin "1") (pinfunction "1_1") (pintype "unspecified"))
      (node (ref "C26") (pin "1") (pinfunction "1_1") (pintype "unspecified"))
      (node (ref "C27") (pin "1") (pinfunction "1_1") (pintype "unspecified"))
      (node (ref "C28") (pin "1") (pinfunction "1_1") (pintype "unspecified"))
      (node (ref "C29") (pin "1") (pinfunction "1_1") (pintype "unspecified"))
      (node (ref "C30") (pin "1") (pinfunction "1_1") (pintype "unspecified"))
      (node (ref "C31") (pin "1") (pinfunction "1_1") (pintype "unspecified"))
      (node (ref "C32") (pin "1") (pinfunction "1_1") (pintype "unspecified"))
      (node (ref "C33") (pin "1") (pinfunction "1_1") (pintype "unspecified"))
      (node (ref "C34") (pin "1") (pinfunction "1_1") (pintype "unspecified"))
      (node (ref "C35") (pin "1") (pinfunction "1_1") (pintype "unspecified"))
      (node (ref "C36") (pin "1") (pinfunction "1_1") (pintype "unspecified"))
      (node (ref "C37") (pin "1") (pinfunction "1_1") (pintype "unspecified"))
      (node (ref "C38") (pin "1") (pinfunction "1_1") (pintype "unspecified"))
      (node (ref "C39") (pin "1") (pinfunction "1_1") (pintype "unspecified"))
      (node (ref "C4") (pin "1") (pinfunction "1_1") (pintype "unspecified"))
      (node (ref "C40") (pin "1") (pinfunction "1_1") (pintype "unspecified"))
      (node (ref "C41") (pin "1") (pinfunction "1_1") (pintype "unspecified"))
      (node (ref "C42") (pin "1") (pinfunction "1_1") (pintype "unspecified"))
      (node (ref "C43") (pin "1") (pinfunction "1_1") (pintype "unspecified"))
      (node (ref "C44") (pin "1") (pinfunction "1_1") (pintype "unspecified"))
      (node (ref "C45") (pin "1") (pinfunction "1_1") (pintype "unspecified"))
      (node (ref "C46") (pin "1") (pinfunction "1_1") (pintype "unspecified"))
      (node (ref "C47") (pin "1") (pinfunction "1_1") (pintype "unspecified"))
      (node (ref "C48") (pin "1") (pinfunction "1_1") (pintype "unspecified"))
      (node (ref "C49") (pin "1") (pinfunction "1_1") (pintype "unspecified"))
      (node (ref "C5") (pin "1") (pinfunction "1_1") (pintype "unspecified"))
      (node (ref "C50") (pin "1") (pinfunction "1_1") (pintype "unspecified"))
      (node (ref "C51") (pin "1") (pinfunction "1_1") (pintype "unspecified"))
      (node (ref "C52") (pin "1") (pinfunction "1_1") (pintype "unspecified"))
      (node (ref "C53") (pin "1") (pinfunction "1_1") (pintype "unspecified"))
      (node (ref "C54") (pin "1") (pinfunction "1_1") (pintype "unspecified"))
      (node (ref "C55") (pin "1") (pinfunction "1_1") (pintype "unspecified"))
      (node (ref "C56") (pin "1") (pinfunction "1_1") (pintype "unspecified"))
      (node (ref "C57") (pin "1") (pinfunction "1_1") (pintype "unspecified"))
      (node (ref "C58") (pin "1") (pinfunction "1_1") (pintype "unspecified"))
      (node (ref "C59") (pin "1") (pinfunction "1_1") (pintype "unspecified"))
      (node (ref "C6") (pin "1") (pinfunction "1_1") (pintype "unspecified"))
      (node (ref "C60") (pin "1") (pinfunction "1_1") (pintype "unspecified"))
      (node (ref "C61") (pin "1") (pinfunction "1_1") (pintype "unspecified"))
      (node (ref "C62") (pin "1") (pinfunction "1_1") (pintype "unspecified"))
      (node (ref "C63") (pin "1") (pinfunction "1_1") (pintype "unspecified"))
      (node (ref "C64") (pin "1") (pinfunction "1_1") (pintype "unspecified"))
      (node (ref "C65") (pin "1") (pinfunction "1_1") (pintype "unspecified"))
      (node (ref "C66") (pin "1") (pinfunction "1_1") (pintype "unspecified"))
      (node (ref "C67") (pin "1") (pinfunction "1_1") (pintype "unspecified"))
      (node (ref "C68") (pin "1") (pinfunction "1_1") (pintype "unspecified"))
      (node (ref "C69") (pin "1") (pinfunction "1_1") (pintype "unspecified"))
      (node (ref "C7") (pin "1") (pinfunction "1_1") (pintype "unspecified"))
      (node (ref "C70") (pin "1") (pinfunction "1_1") (pintype "unspecified"))
      (node (ref "C71") (pin "1") (pinfunction "1_1") (pintype "unspecified"))
      (node (ref "C72") (pin "1") (pinfunction "1_1") (pintype "unspecified"))
      (node (ref "C73") (pin "1") (pinfunction "1_1") (pintype "unspecified"))
      (node (ref "C74") (pin "1") (pinfunction "1_1") (pintype "unspecified"))
      (node (ref "C75") (pin "1") (pinfunction "1_1") (pintype "unspecified"))
      (node (ref "C76") (pin "2") (pinfunction "2_2") (pintype "unspecified"))
      (node (ref "C77") (pin "2") (pinfunction "2_2") (pintype "unspecified"))
      (node (ref "C78") (pin "2") (pinfunction "2_2") (pintype "unspecified"))
      (node (ref "C79") (pin "2") (pinfunction "2_2") (pintype "unspecified"))
      (node (ref "C8") (pin "2") (pinfunction "2_2") (pintype "unspecified"))
      (node (ref "C80") (pin "2") (pinfunction "2_2") (pintype "unspecified"))
      (node (ref "C81") (pin "2") (pinfunction "2_2") (pintype "unspecified"))
      (node (ref "C82") (pin "2") (pinfunction "2_2") (pintype "unspecified"))
      (node (ref "C84") (pin "2") (pinfunction "2_2") (pintype "unspecified"))
      (node (ref "C9") (pin "1") (pinfunction "1_1") (pintype "unspecified"))
      (node (ref "R2") (pin "1") (pinfunction "1_1") (pintype "unspecified"))
      (node (ref "SW1") (pin "VDD") (pinfunction "VDD_VDD") (pintype "unspecified"))
      (node (ref "SW10") (pin "VDD") (pinfunction "VDD_VDD") (pintype "unspecified"))
      (node (ref "SW11") (pin "VDD") (pinfunction "VDD_VDD") (pintype "unspecified"))
      (node (ref "SW12") (pin "VDD") (pinfunction "VDD_VDD") (pintype "unspecified"))
      (node (ref "SW13") (pin "VDD") (pinfunction "VDD_VDD") (pintype "unspecified"))
      (node (ref "SW14") (pin "VDD") (pinfunction "VDD_VDD") (pintype "unspecified"))
      (node (ref "SW15") (pin "VDD") (pinfunction "VDD_VDD") (pintype "unspecified"))
      (node (ref "SW16") (pin "VDD") (pinfunction "VDD_VDD") (pintype "unspecified"))
      (node (ref "SW17") (pin "VDD") (pinfunction "VDD_VDD") (pintype "unspecified"))
      (node (ref "SW18") (pin "VDD") (pinfunction "VDD_VDD") (pintype "unspecified"))
      (node (ref "SW19") (pin "VDD") (pinfunction "VDD_VDD") (pintype "unspecified"))
      (node (ref "SW2") (pin "VDD") (pinfunction "VDD_VDD") (pintype "unspecified"))
      (node (ref "SW20") (pin "VDD") (pinfunction "VDD_VDD") (pintype "unspecified"))
      (node (ref "SW21") (pin "VDD") (pinfunction "VDD_VDD") (pintype "unspecified"))
      (node (ref "SW22") (pin "VDD") (pinfunction "VDD_VDD") (pintype "unspecified"))
      (node (ref "SW23") (pin "VDD") (pinfunction "VDD_VDD") (pintype "unspecified"))
      (node (ref "SW24") (pin "VDD") (pinfunction "VDD_VDD") (pintype "unspecified"))
      (node (ref "SW25") (pin "VDD") (pinfunction "VDD_VDD") (pintype "unspecified"))
      (node (ref "SW26") (pin "VDD") (pinfunction "VDD_VDD") (pintype "unspecified"))
      (node (ref "SW27") (pin "VDD") (pinfunction "VDD_VDD") (pintype "unspecified"))
      (node (ref "SW28") (pin "VDD") (pinfunction "VDD_VDD") (pintype "unspecified"))
      (node (ref "SW29") (pin "VDD") (pinfunction "VDD_VDD") (pintype "unspecified"))
      (node (ref "SW3") (pin "VDD") (pinfunction "VDD_VDD") (pintype "unspecified"))
      (node (ref "SW30") (pin "VDD") (pinfunction "VDD_VDD") (pintype "unspecified"))
      (node (ref "SW31") (pin "VDD") (pinfunction "VDD_VDD") (pintype "unspecified"))
      (node (ref "SW32") (pin "VDD") (pinfunction "VDD_VDD") (pintype "unspecified"))
      (node (ref "SW33") (pin "VDD") (pinfunction "VDD_VDD") (pintype "unspecified"))
      (node (ref "SW34") (pin "VDD") (pinfunction "VDD_VDD") (pintype "unspecified"))
      (node (ref "SW35") (pin "VDD") (pinfunction "VDD_VDD") (pintype "unspecified"))
      (node (ref "SW36") (pin "VDD") (pinfunction "VDD_VDD") (pintype "unspecified"))
      (node (ref "SW37") (pin "VDD") (pinfunction "VDD_VDD") (pintype "unspecified"))
      (node (ref "SW38") (pin "VDD") (pinfunction "VDD_VDD") (pintype "unspecified"))
      (node (ref "SW39") (pin "VDD") (pinfunction "VDD_VDD") (pintype "unspecified"))
      (node (ref "SW4") (pin "VDD") (pinfunction "VDD_VDD") (pintype "unspecified"))
      (node (ref "SW40") (pin "VDD") (pinfunction "VDD_VDD") (pintype "unspecified"))
      (node (ref "SW41") (pin "VDD") (pinfunction "VDD_VDD") (pintype "unspecified"))
      (node (ref "SW42") (pin "VDD") (pinfunction "VDD_VDD") (pintype "unspecified"))
      (node (ref "SW43") (pin "VDD") (pinfunction "VDD_VDD") (pintype "unspecified"))
      (node (ref "SW44") (pin "VDD") (pinfunction "VDD_VDD") (pintype "unspecified"))
      (node (ref "SW45") (pin "VDD") (pinfunction "VDD_VDD") (pintype "unspecified"))
      (node (ref "SW46") (pin "VDD") (pinfunction "VDD_VDD") (pintype "unspecified"))
      (node (ref "SW47") (pin "VDD") (pinfunction "VDD_VDD") (pintype "unspecified"))
      (node (ref "SW48") (pin "VDD") (pinfunction "VDD_VDD") (pintype "unspecified"))
      (node (ref "SW49") (pin "VDD") (pinfunction "VDD_VDD") (pintype "unspecified"))
      (node (ref "SW5") (pin "VDD") (pinfunction "VDD_VDD") (pintype "unspecified"))
      (node (ref "SW50") (pin "VDD") (pinfunction "VDD_VDD") (pintype "unspecified"))
      (node (ref "SW51") (pin "VDD") (pinfunction "VDD_VDD") (pintype "unspecified"))
      (node (ref "SW52") (pin "VDD") (pinfunction "VDD_VDD") (pintype "unspecified"))
      (node (ref "SW53") (pin "VDD") (pinfunction "VDD_VDD") (pintype "unspecified"))
      (node (ref "SW54") (pin "VDD") (pinfunction "VDD_VDD") (pintype "unspecified"))
      (node (ref "SW55") (pin "VDD") (pinfunction "VDD_VDD") (pintype "unspecified"))
      (node (ref "SW56") (pin "VDD") (pinfunction "VDD_VDD") (pintype "unspecified"))
      (node (ref "SW57") (pin "VDD") (pinfunction "VDD_VDD") (pintype "unspecified"))
      (node (ref "SW58") (pin "VDD") (pinfunction "VDD_VDD") (pintype "unspecified"))
      (node (ref "SW59") (pin "VDD") (pinfunction "VDD_VDD") (pintype "unspecified"))
      (node (ref "SW6") (pin "VDD") (pinfunction "VDD_VDD") (pintype "unspecified"))
      (node (ref "SW60") (pin "VDD") (pinfunction "VDD_VDD") (pintype "unspecified"))
      (node (ref "SW61") (pin "VDD") (pinfunction "VDD_VDD") (pintype "unspecified"))
      (node (ref "SW62") (pin "VDD") (pinfunction "VDD_VDD") (pintype "unspecified"))
      (node (ref "SW63") (pin "VDD") (pinfunction "VDD_VDD") (pintype "unspecified"))
      (node (ref "SW64") (pin "VDD") (pinfunction "VDD_VDD") (pintype "unspecified"))
      (node (ref "SW65") (pin "VDD") (pinfunction "VDD_VDD") (pintype "unspecified"))
      (node (ref "SW66") (pin "VDD") (pinfunction "VDD_VDD") (pintype "unspecified"))
      (node (ref "SW67") (pin "VDD") (pinfunction "VDD_VDD") (pintype "unspecified"))
      (node (ref "SW7") (pin "VDD") (pinfunction "VDD_VDD") (pintype "unspecified"))
      (node (ref "SW8") (pin "VDD") (pinfunction "VDD_VDD") (pintype "unspecified"))
      (node (ref "SW9") (pin "VDD") (pinfunction "VDD_VDD") (pintype "unspecified"))
      (node (ref "U1") (pin "14") (pinfunction "VCC_14") (pintype "passive"))
      (node (ref "U1") (pin "2") (pinfunction "UVcc_2") (pintype "passive"))
      (node (ref "U1") (pin "24") (pinfunction "AVCC_24") (pintype "passive"))
      (node (ref "U1") (pin "34") (pinfunction "VCC_34") (pintype "passive"))
      (node (ref "U1") (pin "44") (pinfunction "AVCC_44") (pintype "passive"))
      (node (ref "U1") (pin "7") (pinfunction "VBus_7") (pintype "unspecified"))
      (node (ref "U2") (pin "1") (pinfunction "VDD_1") (pintype "unspecified"))
      (node (ref "U3") (pin "1") (pinfunction "VDD_1") (pintype "unspecified"))
      (node (ref "U4") (pin "1") (pinfunction "VDD_1") (pintype "unspecified"))
      (node (ref "U5") (pin "1") (pinfunction "VDD_1") (pintype "unspecified"))
      (node (ref "U6") (pin "1") (pinfunction "VDD_1") (pintype "unspecified"))
      (node (ref "U7") (pin "1") (pinfunction "VDD_1") (pintype "unspecified"))
      (node (ref "U8") (pin "1") (pinfunction "VDD_1") (pintype "unspecified"))
      (node (ref "U9") (pin "1") (pinfunction "VDD_1") (pintype "unspecified"))
      (node (ref "USBC1") (pin "A4") (pinfunction "VBUS_A4") (pintype "unspecified"))
      (node (ref "USBC1") (pin "A9") (pinfunction "VBUS_A9") (pintype "unspecified"))
      (node (ref "USBC1") (pin "B4") (pinfunction "VBUS_B4") (pintype "unspecified"))
      (node (ref "USBC1") (pin "B9") (pinfunction "VBUS_B9") (pintype "unspecified"))
    )
    (net (code "176") (name "unconnected-(SW68-Pad6)") (class "Default")
      (node (ref "SW68") (pin "6") (pinfunction "6_6") (pintype "unspecified+no_connect"))
    )
    (net (code "177") (name "unconnected-(SW68-Pad7)") (class "Default")
      (node (ref "SW68") (pin "7") (pinfunction "7_7") (pintype "unspecified+no_connect"))
    )
    (net (code "178") (name "unconnected-(U1-PB1_(PCINT1{slash}SCLK)-Pad9)") (class "Default")
      (node (ref "U1") (pin "9") (pinfunction "PB1_(PCINT1/SCLK)_9") (pintype "bidirectional+no_connect"))
    )
    (net (code "179") (name "unconnected-(U1-PD4(ICP1{slash}ADC8)-Pad25)") (class "Default")
      (node (ref "U1") (pin "25") (pinfunction "PD4(ICP1/ADC8)_25") (pintype "bidirectional"))
    )
    (net (code "180") (name "unconnected-(U1-PE6_(INT.6{slash}AIN0)-Pad1)") (class "Default")
      (node (ref "U1") (pin "1") (pinfunction "PE6_(INT.6/AIN0)_1") (pintype "bidirectional+no_connect"))
    )
    (net (code "181") (name "unconnected-(U7-DOUT-Pad2)") (class "Default")
      (node (ref "U7") (pin "2") (pinfunction "DOUT_2") (pintype "unspecified+no_connect"))
    )
    (net (code "182") (name "unconnected-(USBC1-CC1-PadA5)") (class "Default")
      (node (ref "USBC1") (pin "A5") (pinfunction "CC1_A5") (pintype "unspecified+no_connect"))
    )
    (net (code "183") (name "unconnected-(USBC1-CC2-PadB5)") (class "Default")
      (node (ref "USBC1") (pin "B5") (pinfunction "CC2_B5") (pintype "unspecified+no_connect"))
    )
    (net (code "184") (name "unconnected-(USBC1-SBU1-PadA8)") (class "Default")
      (node (ref "USBC1") (pin "A8") (pinfunction "SBU1_A8") (pintype "unspecified+no_connect"))
    )
    (net (code "185") (name "unconnected-(USBC1-SBU2-PadB8)") (class "Default")
      (node (ref "USBC1") (pin "B8") (pinfunction "SBU2_B8") (pintype "unspecified+no_connect"))
    )
  )
)
